# icyradio-exp-mmw-int-base.net
KiCad netlist of a schematic drawn in EAGLE
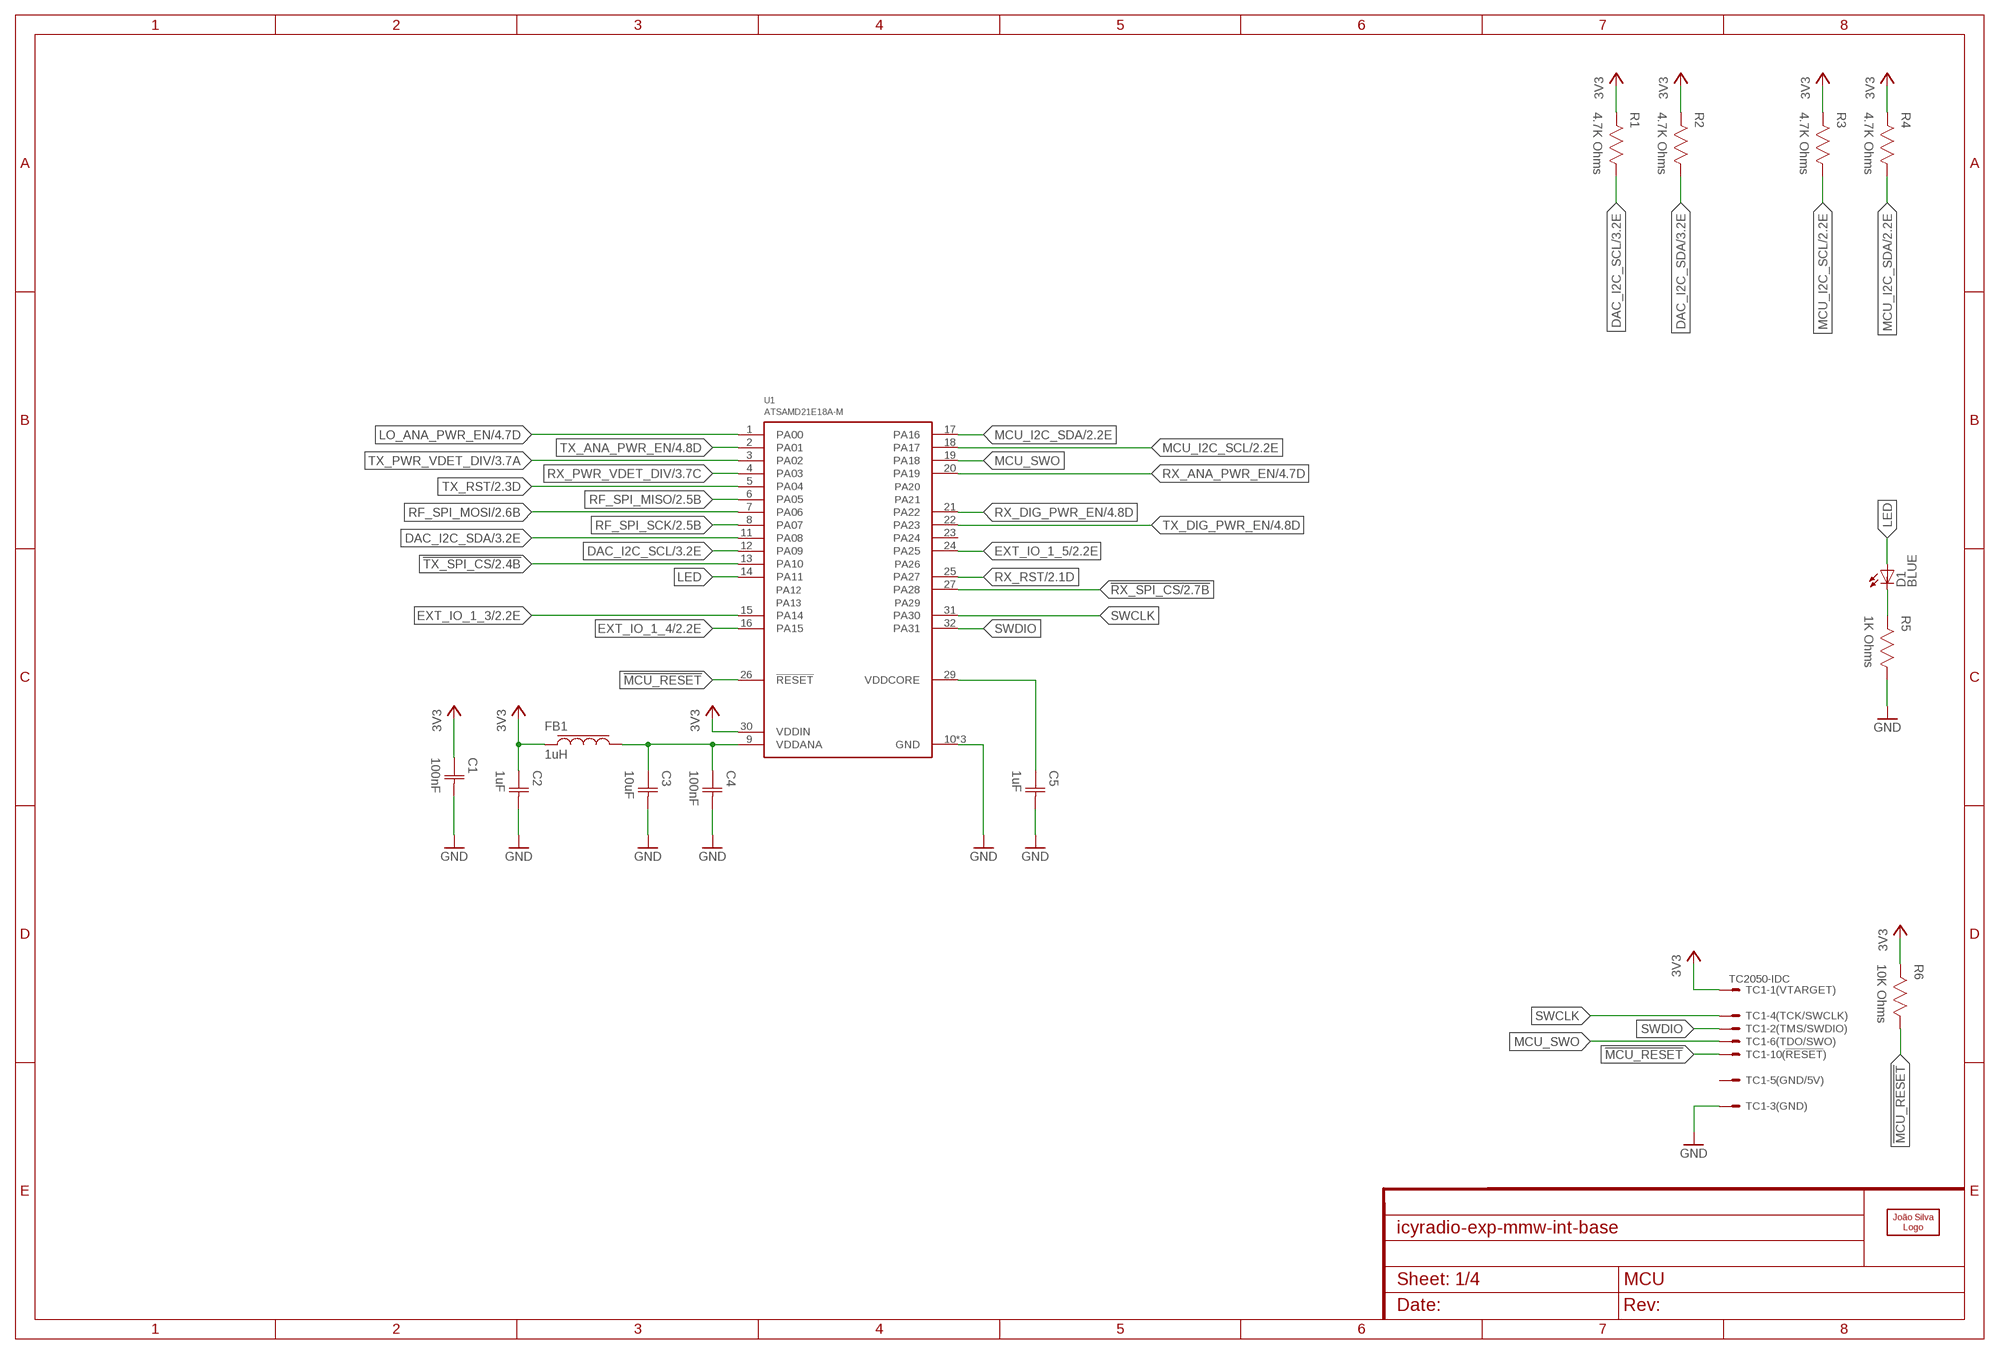
[diagram p0: schematic, sheet 1]
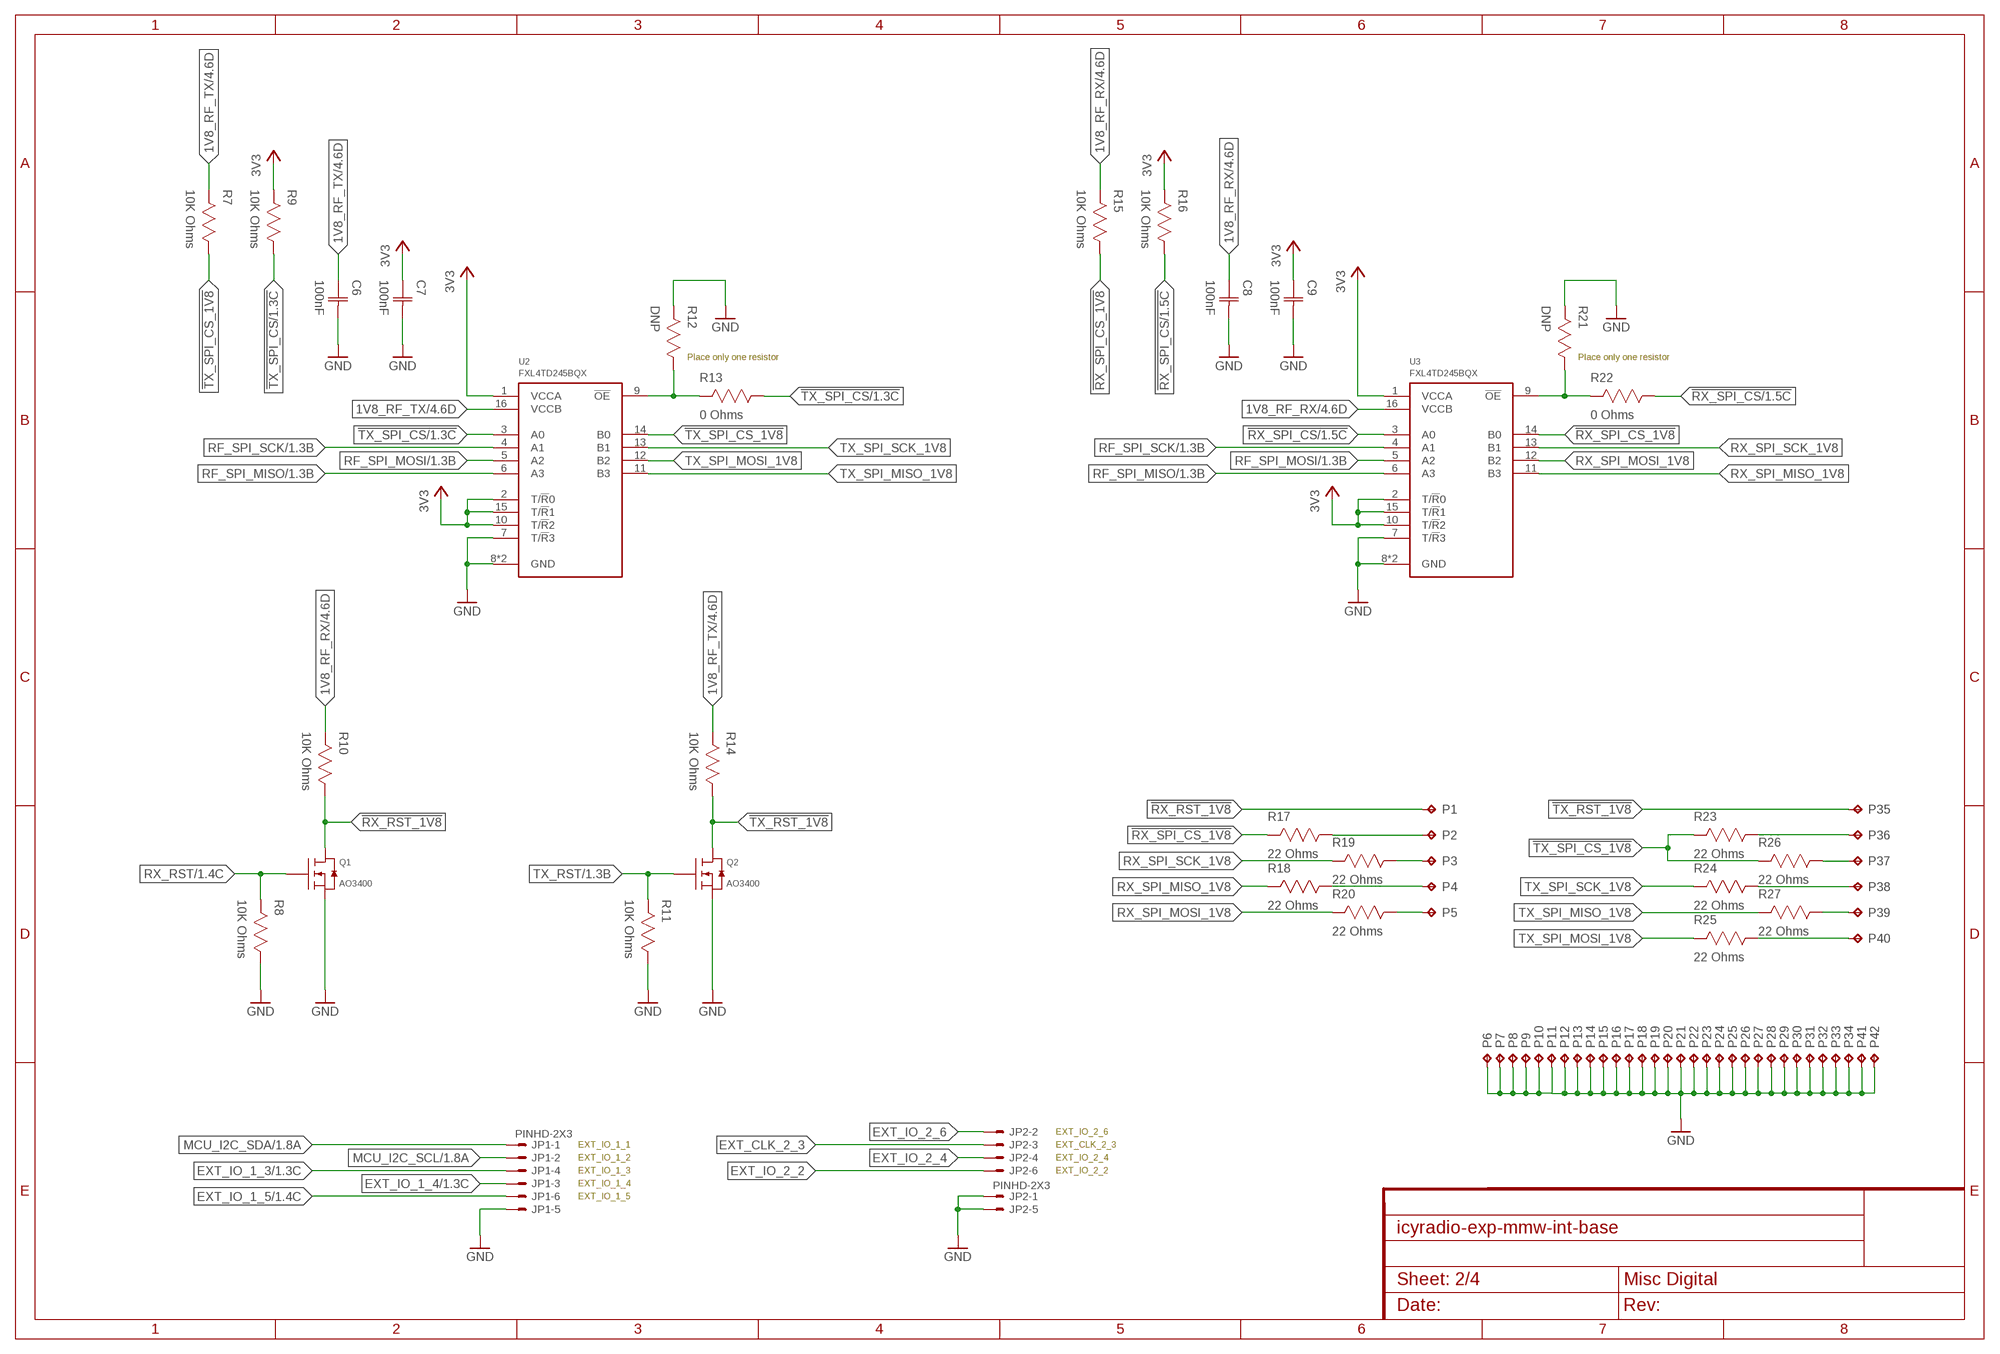
[diagram p1: schematic, sheet 2]
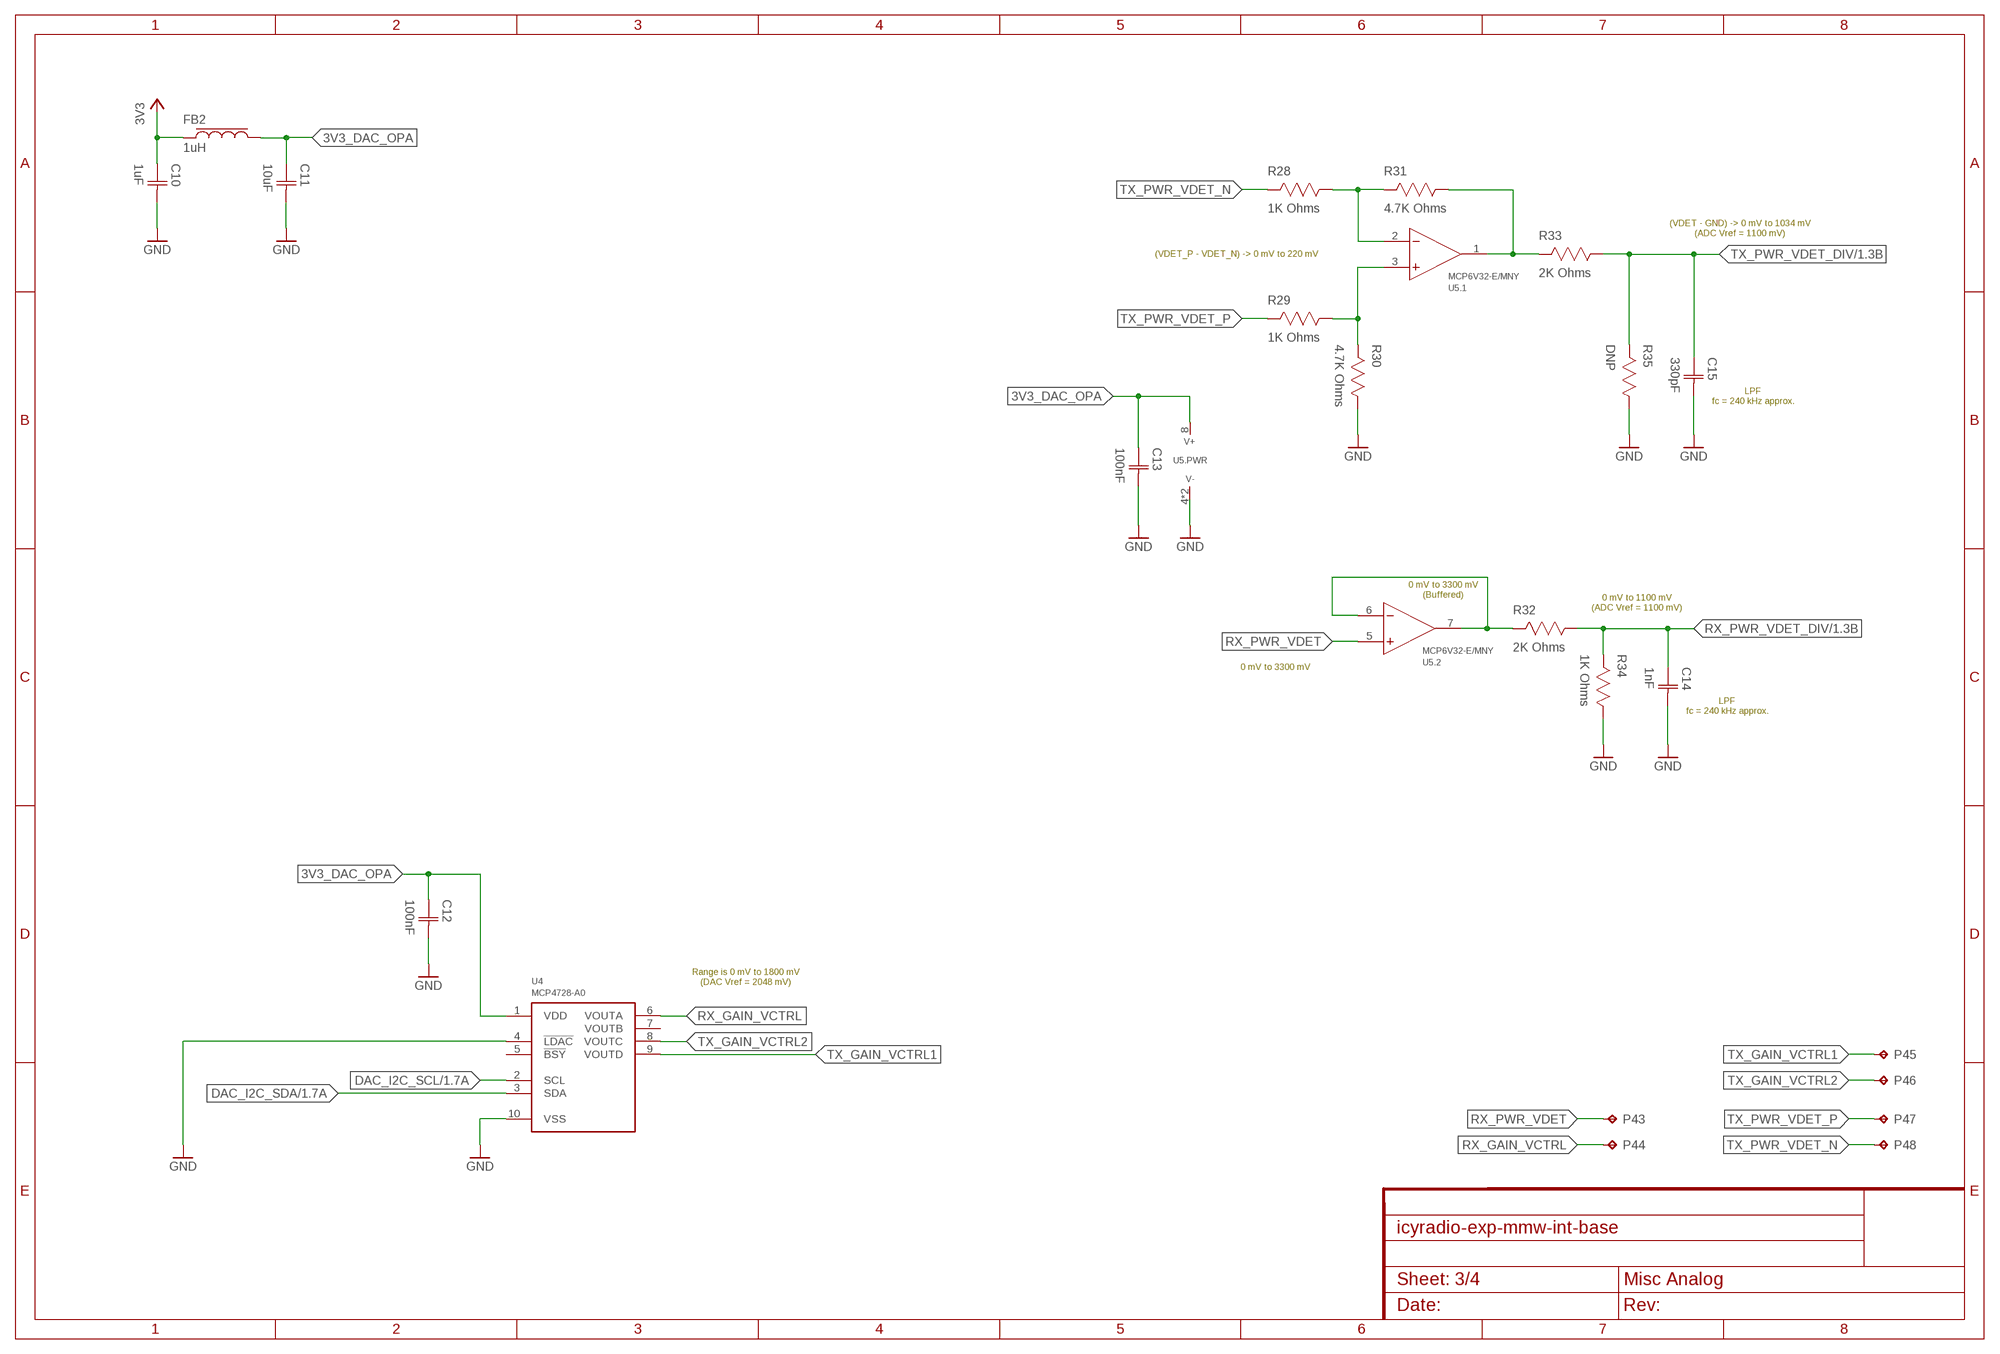
[diagram p2: schematic, sheet 3]
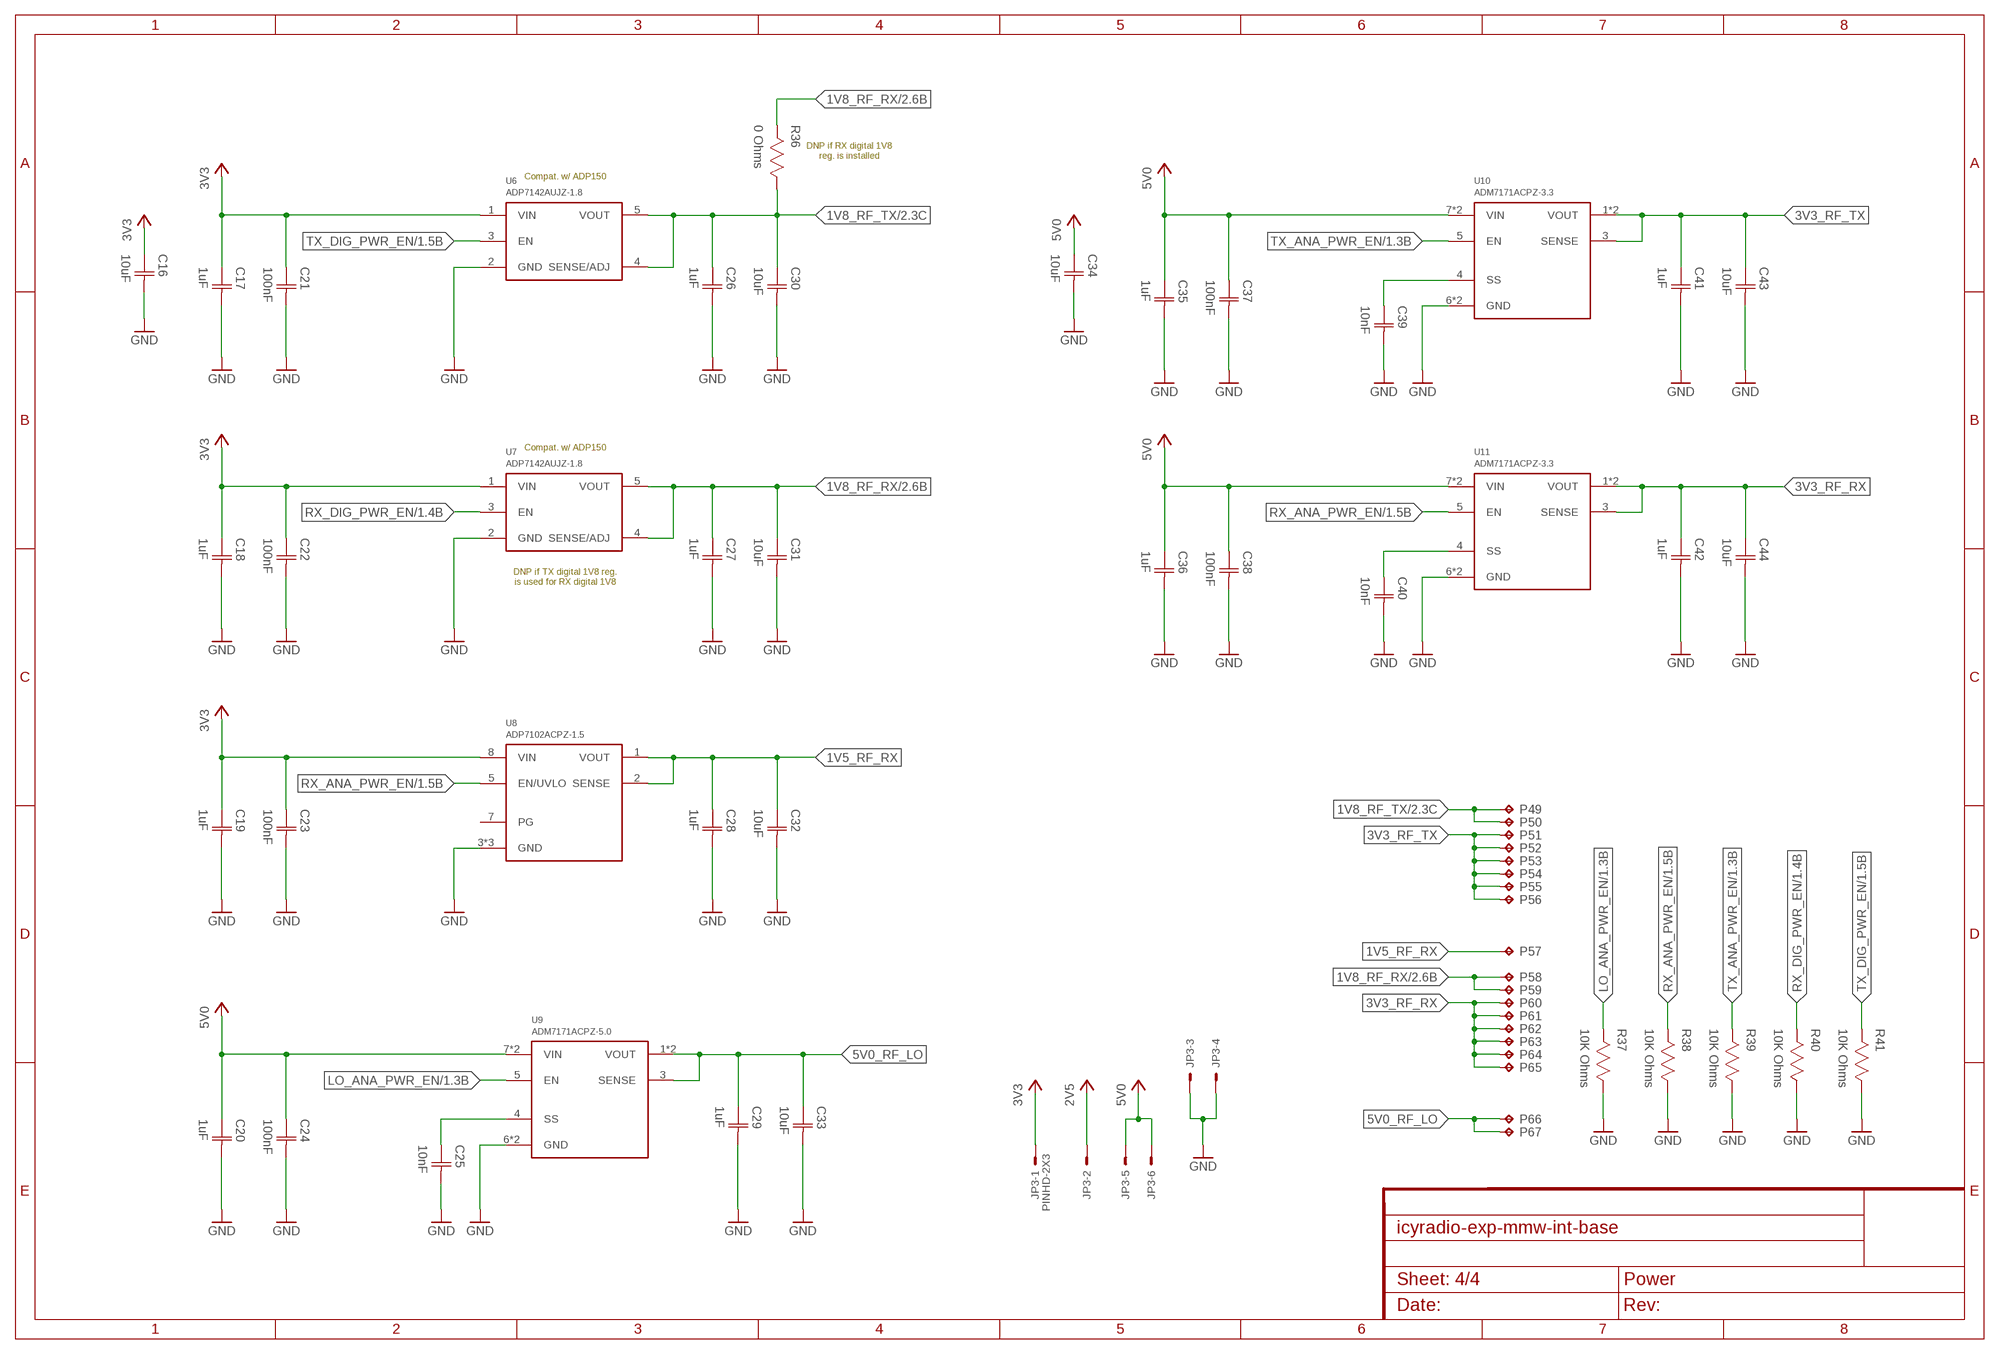
[diagram p3: schematic, sheet 4]

(export (version "E")
  (design (tool "Eeschema 10.0.6"))
  (components
    (comp (ref "C1")
      (value "100nF")
      (footprint "eagle-import:CAP0402")
      (libsource (lib "eagle-import") (part "CAPACITOR-0402"))
    )
    (comp (ref "C2")
      (value "1uF")
      (footprint "eagle-import:CAP0402")
      (libsource (lib "eagle-import") (part "CAPACITOR-0402"))
    )
    (comp (ref "C3")
      (value "10uF")
      (footprint "eagle-import:CAP0402")
      (libsource (lib "eagle-import") (part "CAPACITOR-0402"))
    )
    (comp (ref "C4")
      (value "100nF")
      (footprint "eagle-import:CAP0402")
      (libsource (lib "eagle-import") (part "CAPACITOR-0402"))
    )
    (comp (ref "C5")
      (value "1uF")
      (footprint "eagle-import:CAP0402")
      (libsource (lib "eagle-import") (part "CAPACITOR-0402"))
    )
    (comp (ref "D1")
      (value "LED0603")
      (footprint "eagle-import:0603")
      (fields (field (name "COLOR") "BLUE"))
      (libsource (lib "eagle-import") (part "LED0603"))
    )
    (comp (ref "FB1")
      (value "1uH")
      (footprint "eagle-import:IND0603")
      (libsource (lib "eagle-import") (part "FERRITE-0603"))
    )
    (comp (ref "LOGO1")
      (value "JSILVA-5MM")
      (footprint "eagle-import:JSILVA_5MM")
      (libsource (lib "eagle-import") (part "JSILVA-5MM"))
    )
    (comp (ref "R1")
      (value "4.7K Ohms")
      (footprint "eagle-import:RES0402")
      (libsource (lib "eagle-import") (part "RESISTOR-0402"))
    )
    (comp (ref "R2")
      (value "4.7K Ohms")
      (footprint "eagle-import:RES0402")
      (libsource (lib "eagle-import") (part "RESISTOR-0402"))
    )
    (comp (ref "R3")
      (value "4.7K Ohms")
      (footprint "eagle-import:RES0402")
      (libsource (lib "eagle-import") (part "RESISTOR-0402"))
    )
    (comp (ref "R4")
      (value "4.7K Ohms")
      (footprint "eagle-import:RES0402")
      (libsource (lib "eagle-import") (part "RESISTOR-0402"))
    )
    (comp (ref "R5")
      (value "1K Ohms")
      (footprint "eagle-import:RES0402")
      (libsource (lib "eagle-import") (part "RESISTOR-0402"))
    )
    (comp (ref "R6")
      (value "10K Ohms")
      (footprint "eagle-import:RES0402")
      (libsource (lib "eagle-import") (part "RESISTOR-0402"))
    )
    (comp (ref "TC1")
      (value "TC2050-IDC")
      (footprint "eagle-import:TC2050-IDC")
      (libsource (lib "eagle-import") (part "TC2050-IDC"))
    )
    (comp (ref "U1")
      (value "ATSAMD21E18A-M")
      (footprint "eagle-import:QFN32")
      (libsource (lib "eagle-import") (part "ATSAMD2-?M1E18A"))
    )
    (comp (ref "C6")
      (value "100nF")
      (footprint "eagle-import:CAP0402")
      (libsource (lib "eagle-import") (part "CAPACITOR-0402"))
    )
    (comp (ref "C7")
      (value "100nF")
      (footprint "eagle-import:CAP0402")
      (libsource (lib "eagle-import") (part "CAPACITOR-0402"))
    )
    (comp (ref "C8")
      (value "100nF")
      (footprint "eagle-import:CAP0402")
      (libsource (lib "eagle-import") (part "CAPACITOR-0402"))
    )
    (comp (ref "C9")
      (value "100nF")
      (footprint "eagle-import:CAP0402")
      (libsource (lib "eagle-import") (part "CAPACITOR-0402"))
    )
    (comp (ref "JP1")
      (value "PINHD-2X3")
      (footprint "eagle-import:2X03")
      (libsource (lib "eagle-import") (part "PINHD-2X3"))
    )
    (comp (ref "JP2")
      (value "PINHD-2X3")
      (footprint "eagle-import:2X03")
      (libsource (lib "eagle-import") (part "PINHD-2X3"))
    )
    (comp (ref "P1")
      (value "CHOLE-0.9MM-LAND")
      (footprint "eagle-import:CAST_HOLE_0P9MM_LAND")
      (libsource (lib "eagle-import") (part "CHOLE-0.9MM-LAND"))
    )
    (comp (ref "P2")
      (value "CHOLE-0.9MM-LAND")
      (footprint "eagle-import:CAST_HOLE_0P9MM_LAND")
      (libsource (lib "eagle-import") (part "CHOLE-0.9MM-LAND"))
    )
    (comp (ref "P3")
      (value "CHOLE-0.9MM-LAND")
      (footprint "eagle-import:CAST_HOLE_0P9MM_LAND")
      (libsource (lib "eagle-import") (part "CHOLE-0.9MM-LAND"))
    )
    (comp (ref "P4")
      (value "CHOLE-0.9MM-LAND")
      (footprint "eagle-import:CAST_HOLE_0P9MM_LAND")
      (libsource (lib "eagle-import") (part "CHOLE-0.9MM-LAND"))
    )
    (comp (ref "P5")
      (value "CHOLE-0.9MM-LAND")
      (footprint "eagle-import:CAST_HOLE_0P9MM_LAND")
      (libsource (lib "eagle-import") (part "CHOLE-0.9MM-LAND"))
    )
    (comp (ref "P6")
      (value "CHOLE-0.9MM-LAND")
      (footprint "eagle-import:CAST_HOLE_0P9MM_LAND")
      (libsource (lib "eagle-import") (part "CHOLE-0.9MM-LAND"))
    )
    (comp (ref "P7")
      (value "CHOLE-0.9MM-LAND")
      (footprint "eagle-import:CAST_HOLE_0P9MM_LAND")
      (libsource (lib "eagle-import") (part "CHOLE-0.9MM-LAND"))
    )
    (comp (ref "P8")
      (value "CHOLE-0.9MM-LAND")
      (footprint "eagle-import:CAST_HOLE_0P9MM_LAND")
      (libsource (lib "eagle-import") (part "CHOLE-0.9MM-LAND"))
    )
    (comp (ref "P9")
      (value "CHOLE-0.9MM-LAND")
      (footprint "eagle-import:CAST_HOLE_0P9MM_LAND")
      (libsource (lib "eagle-import") (part "CHOLE-0.9MM-LAND"))
    )
    (comp (ref "P10")
      (value "CHOLE-0.9MM-LAND")
      (footprint "eagle-import:CAST_HOLE_0P9MM_LAND")
      (libsource (lib "eagle-import") (part "CHOLE-0.9MM-LAND"))
    )
    (comp (ref "P11")
      (value "CHOLE-0.9MM-LAND")
      (footprint "eagle-import:CAST_HOLE_0P9MM_LAND")
      (libsource (lib "eagle-import") (part "CHOLE-0.9MM-LAND"))
    )
    (comp (ref "P12")
      (value "CHOLE-0.9MM-LAND")
      (footprint "eagle-import:CAST_HOLE_0P9MM_LAND")
      (libsource (lib "eagle-import") (part "CHOLE-0.9MM-LAND"))
    )
    (comp (ref "P13")
      (value "CHOLE-0.9MM-LAND")
      (footprint "eagle-import:CAST_HOLE_0P9MM_LAND")
      (libsource (lib "eagle-import") (part "CHOLE-0.9MM-LAND"))
    )
    (comp (ref "P14")
      (value "CHOLE-0.9MM-LAND")
      (footprint "eagle-import:CAST_HOLE_0P9MM_LAND")
      (libsource (lib "eagle-import") (part "CHOLE-0.9MM-LAND"))
    )
    (comp (ref "P15")
      (value "CHOLE-0.9MM-LAND")
      (footprint "eagle-import:CAST_HOLE_0P9MM_LAND")
      (libsource (lib "eagle-import") (part "CHOLE-0.9MM-LAND"))
    )
    (comp (ref "P16")
      (value "CHOLE-0.9MM-LAND")
      (footprint "eagle-import:CAST_HOLE_0P9MM_LAND")
      (libsource (lib "eagle-import") (part "CHOLE-0.9MM-LAND"))
    )
    (comp (ref "P17")
      (value "CHOLE-0.9MM-LAND")
      (footprint "eagle-import:CAST_HOLE_0P9MM_LAND")
      (libsource (lib "eagle-import") (part "CHOLE-0.9MM-LAND"))
    )
    (comp (ref "P18")
      (value "CHOLE-0.9MM-LAND")
      (footprint "eagle-import:CAST_HOLE_0P9MM_LAND")
      (libsource (lib "eagle-import") (part "CHOLE-0.9MM-LAND"))
    )
    (comp (ref "P19")
      (value "CHOLE-0.9MM-LAND")
      (footprint "eagle-import:CAST_HOLE_0P9MM_LAND")
      (libsource (lib "eagle-import") (part "CHOLE-0.9MM-LAND"))
    )
    (comp (ref "P20")
      (value "CHOLE-0.9MM-LAND")
      (footprint "eagle-import:CAST_HOLE_0P9MM_LAND")
      (libsource (lib "eagle-import") (part "CHOLE-0.9MM-LAND"))
    )
    (comp (ref "P21")
      (value "CHOLE-0.9MM-LAND")
      (footprint "eagle-import:CAST_HOLE_0P9MM_LAND")
      (libsource (lib "eagle-import") (part "CHOLE-0.9MM-LAND"))
    )
    (comp (ref "P22")
      (value "CHOLE-0.9MM-LAND")
      (footprint "eagle-import:CAST_HOLE_0P9MM_LAND")
      (libsource (lib "eagle-import") (part "CHOLE-0.9MM-LAND"))
    )
    (comp (ref "P23")
      (value "CHOLE-0.9MM-LAND")
      (footprint "eagle-import:CAST_HOLE_0P9MM_LAND")
      (libsource (lib "eagle-import") (part "CHOLE-0.9MM-LAND"))
    )
    (comp (ref "P24")
      (value "CHOLE-0.9MM-LAND")
      (footprint "eagle-import:CAST_HOLE_0P9MM_LAND")
      (libsource (lib "eagle-import") (part "CHOLE-0.9MM-LAND"))
    )
    (comp (ref "P25")
      (value "CHOLE-0.9MM-LAND")
      (footprint "eagle-import:CAST_HOLE_0P9MM_LAND")
      (libsource (lib "eagle-import") (part "CHOLE-0.9MM-LAND"))
    )
    (comp (ref "P26")
      (value "CHOLE-0.9MM-LAND")
      (footprint "eagle-import:CAST_HOLE_0P9MM_LAND")
      (libsource (lib "eagle-import") (part "CHOLE-0.9MM-LAND"))
    )
    (comp (ref "P27")
      (value "CHOLE-0.9MM-LAND")
      (footprint "eagle-import:CAST_HOLE_0P9MM_LAND")
      (libsource (lib "eagle-import") (part "CHOLE-0.9MM-LAND"))
    )
    (comp (ref "P28")
      (value "CHOLE-0.9MM-LAND")
      (footprint "eagle-import:CAST_HOLE_0P9MM_LAND")
      (libsource (lib "eagle-import") (part "CHOLE-0.9MM-LAND"))
    )
    (comp (ref "P29")
      (value "CHOLE-0.9MM-LAND")
      (footprint "eagle-import:CAST_HOLE_0P9MM_LAND")
      (libsource (lib "eagle-import") (part "CHOLE-0.9MM-LAND"))
    )
    (comp (ref "P30")
      (value "CHOLE-0.9MM-LAND")
      (footprint "eagle-import:CAST_HOLE_0P9MM_LAND")
      (libsource (lib "eagle-import") (part "CHOLE-0.9MM-LAND"))
    )
    (comp (ref "P31")
      (value "CHOLE-0.9MM-LAND")
      (footprint "eagle-import:CAST_HOLE_0P9MM_LAND")
      (libsource (lib "eagle-import") (part "CHOLE-0.9MM-LAND"))
    )
    (comp (ref "P32")
      (value "CHOLE-0.9MM-LAND")
      (footprint "eagle-import:CAST_HOLE_0P9MM_LAND")
      (libsource (lib "eagle-import") (part "CHOLE-0.9MM-LAND"))
    )
    (comp (ref "P33")
      (value "CHOLE-0.9MM-LAND")
      (footprint "eagle-import:CAST_HOLE_0P9MM_LAND")
      (libsource (lib "eagle-import") (part "CHOLE-0.9MM-LAND"))
    )
    (comp (ref "P34")
      (value "CHOLE-0.9MM-LAND")
      (footprint "eagle-import:CAST_HOLE_0P9MM_LAND")
      (libsource (lib "eagle-import") (part "CHOLE-0.9MM-LAND"))
    )
    (comp (ref "P35")
      (value "CHOLE-0.9MM-LAND")
      (footprint "eagle-import:CAST_HOLE_0P9MM_LAND")
      (libsource (lib "eagle-import") (part "CHOLE-0.9MM-LAND"))
    )
    (comp (ref "P36")
      (value "CHOLE-0.9MM-LAND")
      (footprint "eagle-import:CAST_HOLE_0P9MM_LAND")
      (libsource (lib "eagle-import") (part "CHOLE-0.9MM-LAND"))
    )
    (comp (ref "P37")
      (value "CHOLE-0.9MM-LAND")
      (footprint "eagle-import:CAST_HOLE_0P9MM_LAND")
      (libsource (lib "eagle-import") (part "CHOLE-0.9MM-LAND"))
    )
    (comp (ref "P38")
      (value "CHOLE-0.9MM-LAND")
      (footprint "eagle-import:CAST_HOLE_0P9MM_LAND")
      (libsource (lib "eagle-import") (part "CHOLE-0.9MM-LAND"))
    )
    (comp (ref "P39")
      (value "CHOLE-0.9MM-LAND")
      (footprint "eagle-import:CAST_HOLE_0P9MM_LAND")
      (libsource (lib "eagle-import") (part "CHOLE-0.9MM-LAND"))
    )
    (comp (ref "P40")
      (value "CHOLE-0.9MM-LAND")
      (footprint "eagle-import:CAST_HOLE_0P9MM_LAND")
      (libsource (lib "eagle-import") (part "CHOLE-0.9MM-LAND"))
    )
    (comp (ref "P41")
      (value "CHOLE-0.9MM-LAND")
      (footprint "eagle-import:CAST_HOLE_0P9MM_LAND")
      (libsource (lib "eagle-import") (part "CHOLE-0.9MM-LAND"))
    )
    (comp (ref "P42")
      (value "CHOLE-0.9MM-LAND")
      (footprint "eagle-import:CAST_HOLE_0P9MM_LAND")
      (libsource (lib "eagle-import") (part "CHOLE-0.9MM-LAND"))
    )
    (comp (ref "Q1")
      (value "AO3400")
      (footprint "eagle-import:SOT23")
      (libsource (lib "eagle-import") (part "AO3400"))
    )
    (comp (ref "Q2")
      (value "AO3400")
      (footprint "eagle-import:SOT23")
      (libsource (lib "eagle-import") (part "AO3400"))
    )
    (comp (ref "R7")
      (value "10K Ohms")
      (footprint "eagle-import:RES0402")
      (libsource (lib "eagle-import") (part "RESISTOR-0402"))
    )
    (comp (ref "R8")
      (value "10K Ohms")
      (footprint "eagle-import:RES0402")
      (libsource (lib "eagle-import") (part "RESISTOR-0402"))
    )
    (comp (ref "R9")
      (value "10K Ohms")
      (footprint "eagle-import:RES0402")
      (libsource (lib "eagle-import") (part "RESISTOR-0402"))
    )
    (comp (ref "R10")
      (value "10K Ohms")
      (footprint "eagle-import:RES0402")
      (libsource (lib "eagle-import") (part "RESISTOR-0402"))
    )
    (comp (ref "R11")
      (value "10K Ohms")
      (footprint "eagle-import:RES0402")
      (libsource (lib "eagle-import") (part "RESISTOR-0402"))
    )
    (comp (ref "R12")
      (value "DNP")
      (footprint "eagle-import:RES0402")
      (libsource (lib "eagle-import") (part "RESISTOR-0402"))
    )
    (comp (ref "R13")
      (value "0 Ohms")
      (footprint "eagle-import:RES0402")
      (libsource (lib "eagle-import") (part "RESISTOR-0402"))
    )
    (comp (ref "R14")
      (value "10K Ohms")
      (footprint "eagle-import:RES0402")
      (libsource (lib "eagle-import") (part "RESISTOR-0402"))
    )
    (comp (ref "R15")
      (value "10K Ohms")
      (footprint "eagle-import:RES0402")
      (libsource (lib "eagle-import") (part "RESISTOR-0402"))
    )
    (comp (ref "R16")
      (value "10K Ohms")
      (footprint "eagle-import:RES0402")
      (libsource (lib "eagle-import") (part "RESISTOR-0402"))
    )
    (comp (ref "R17")
      (value "22 Ohms")
      (footprint "eagle-import:RES0402")
      (libsource (lib "eagle-import") (part "RESISTOR-0402"))
    )
    (comp (ref "R18")
      (value "22 Ohms")
      (footprint "eagle-import:RES0402")
      (libsource (lib "eagle-import") (part "RESISTOR-0402"))
    )
    (comp (ref "R19")
      (value "22 Ohms")
      (footprint "eagle-import:RES0402")
      (libsource (lib "eagle-import") (part "RESISTOR-0402"))
    )
    (comp (ref "R20")
      (value "22 Ohms")
      (footprint "eagle-import:RES0402")
      (libsource (lib "eagle-import") (part "RESISTOR-0402"))
    )
    (comp (ref "R21")
      (value "DNP")
      (footprint "eagle-import:RES0402")
      (libsource (lib "eagle-import") (part "RESISTOR-0402"))
    )
    (comp (ref "R22")
      (value "0 Ohms")
      (footprint "eagle-import:RES0402")
      (libsource (lib "eagle-import") (part "RESISTOR-0402"))
    )
    (comp (ref "R23")
      (value "22 Ohms")
      (footprint "eagle-import:RES0402")
      (libsource (lib "eagle-import") (part "RESISTOR-0402"))
    )
    (comp (ref "R24")
      (value "22 Ohms")
      (footprint "eagle-import:RES0402")
      (libsource (lib "eagle-import") (part "RESISTOR-0402"))
    )
    (comp (ref "R25")
      (value "22 Ohms")
      (footprint "eagle-import:RES0402")
      (libsource (lib "eagle-import") (part "RESISTOR-0402"))
    )
    (comp (ref "R26")
      (value "22 Ohms")
      (footprint "eagle-import:RES0402")
      (libsource (lib "eagle-import") (part "RESISTOR-0402"))
    )
    (comp (ref "R27")
      (value "22 Ohms")
      (footprint "eagle-import:RES0402")
      (libsource (lib "eagle-import") (part "RESISTOR-0402"))
    )
    (comp (ref "U2")
      (value "FXL4TD245BQX")
      (footprint "eagle-import:DQFN16")
      (libsource (lib "eagle-import") (part "FXL4TD245BQX"))
    )
    (comp (ref "U3")
      (value "FXL4TD245BQX")
      (footprint "eagle-import:DQFN16")
      (libsource (lib "eagle-import") (part "FXL4TD245BQX"))
    )
    (comp (ref "C16")
      (value "10uF")
      (footprint "eagle-import:CAP0603")
      (libsource (lib "eagle-import") (part "CAPACITOR-0603"))
    )
    (comp (ref "C17")
      (value "1uF")
      (footprint "eagle-import:CAP0402")
      (libsource (lib "eagle-import") (part "CAPACITOR-0402"))
    )
    (comp (ref "C18")
      (value "1uF")
      (footprint "eagle-import:CAP0402")
      (libsource (lib "eagle-import") (part "CAPACITOR-0402"))
    )
    (comp (ref "C19")
      (value "1uF")
      (footprint "eagle-import:CAP0402")
      (libsource (lib "eagle-import") (part "CAPACITOR-0402"))
    )
    (comp (ref "C20")
      (value "1uF")
      (footprint "eagle-import:CAP0402")
      (libsource (lib "eagle-import") (part "CAPACITOR-0402"))
    )
    (comp (ref "C21")
      (value "100nF")
      (footprint "eagle-import:CAP0402")
      (libsource (lib "eagle-import") (part "CAPACITOR-0402"))
    )
    (comp (ref "C22")
      (value "100nF")
      (footprint "eagle-import:CAP0402")
      (libsource (lib "eagle-import") (part "CAPACITOR-0402"))
    )
    (comp (ref "C23")
      (value "100nF")
      (footprint "eagle-import:CAP0402")
      (libsource (lib "eagle-import") (part "CAPACITOR-0402"))
    )
    (comp (ref "C24")
      (value "100nF")
      (footprint "eagle-import:CAP0402")
      (libsource (lib "eagle-import") (part "CAPACITOR-0402"))
    )
    (comp (ref "C25")
      (value "10nF")
      (footprint "eagle-import:CAP0402")
      (libsource (lib "eagle-import") (part "CAPACITOR-0402"))
    )
    (comp (ref "C26")
      (value "1uF")
      (footprint "eagle-import:CAP0402")
      (libsource (lib "eagle-import") (part "CAPACITOR-0402"))
    )
    (comp (ref "C27")
      (value "1uF")
      (footprint "eagle-import:CAP0402")
      (libsource (lib "eagle-import") (part "CAPACITOR-0402"))
    )
    (comp (ref "C28")
      (value "1uF")
      (footprint "eagle-import:CAP0402")
      (libsource (lib "eagle-import") (part "CAPACITOR-0402"))
    )
    (comp (ref "C29")
      (value "1uF")
      (footprint "eagle-import:CAP0402")
      (libsource (lib "eagle-import") (part "CAPACITOR-0402"))
    )
    (comp (ref "C30")
      (value "10uF")
      (footprint "eagle-import:CAP0402")
      (libsource (lib "eagle-import") (part "CAPACITOR-0402"))
    )
    (comp (ref "C31")
      (value "10uF")
      (footprint "eagle-import:CAP0402")
      (libsource (lib "eagle-import") (part "CAPACITOR-0402"))
    )
    (comp (ref "C32")
      (value "10uF")
      (footprint "eagle-import:CAP0402")
      (libsource (lib "eagle-import") (part "CAPACITOR-0402"))
    )
    (comp (ref "C33")
      (value "10uF")
      (footprint "eagle-import:CAP0402")
      (libsource (lib "eagle-import") (part "CAPACITOR-0402"))
    )
    (comp (ref "C34")
      (value "10uF")
      (footprint "eagle-import:CAP0603")
      (libsource (lib "eagle-import") (part "CAPACITOR-0603"))
    )
    (comp (ref "C35")
      (value "1uF")
      (footprint "eagle-import:CAP0402")
      (libsource (lib "eagle-import") (part "CAPACITOR-0402"))
    )
    (comp (ref "C36")
      (value "1uF")
      (footprint "eagle-import:CAP0402")
      (libsource (lib "eagle-import") (part "CAPACITOR-0402"))
    )
    (comp (ref "C37")
      (value "100nF")
      (footprint "eagle-import:CAP0402")
      (libsource (lib "eagle-import") (part "CAPACITOR-0402"))
    )
    (comp (ref "C38")
      (value "100nF")
      (footprint "eagle-import:CAP0402")
      (libsource (lib "eagle-import") (part "CAPACITOR-0402"))
    )
    (comp (ref "C39")
      (value "10nF")
      (footprint "eagle-import:CAP0402")
      (libsource (lib "eagle-import") (part "CAPACITOR-0402"))
    )
    (comp (ref "C40")
      (value "10nF")
      (footprint "eagle-import:CAP0402")
      (libsource (lib "eagle-import") (part "CAPACITOR-0402"))
    )
    (comp (ref "C41")
      (value "1uF")
      (footprint "eagle-import:CAP0402")
      (libsource (lib "eagle-import") (part "CAPACITOR-0402"))
    )
    (comp (ref "C42")
      (value "1uF")
      (footprint "eagle-import:CAP0402")
      (libsource (lib "eagle-import") (part "CAPACITOR-0402"))
    )
    (comp (ref "C43")
      (value "10uF")
      (footprint "eagle-import:CAP0402")
      (libsource (lib "eagle-import") (part "CAPACITOR-0402"))
    )
    (comp (ref "C44")
      (value "10uF")
      (footprint "eagle-import:CAP0402")
      (libsource (lib "eagle-import") (part "CAPACITOR-0402"))
    )
    (comp (ref "JP3")
      (value "PINHD-2X3")
      (footprint "eagle-import:2X03")
      (libsource (lib "eagle-import") (part "PINHD-2X3"))
    )
    (comp (ref "P49")
      (value "CHOLE-0.9MM-LAND")
      (footprint "eagle-import:CAST_HOLE_0P9MM_LAND")
      (libsource (lib "eagle-import") (part "CHOLE-0.9MM-LAND"))
    )
    (comp (ref "P50")
      (value "CHOLE-0.9MM-LAND")
      (footprint "eagle-import:CAST_HOLE_0P9MM_LAND")
      (libsource (lib "eagle-import") (part "CHOLE-0.9MM-LAND"))
    )
    (comp (ref "P51")
      (value "CHOLE-0.9MM-LAND")
      (footprint "eagle-import:CAST_HOLE_0P9MM_LAND")
      (libsource (lib "eagle-import") (part "CHOLE-0.9MM-LAND"))
    )
    (comp (ref "P52")
      (value "CHOLE-0.9MM-LAND")
      (footprint "eagle-import:CAST_HOLE_0P9MM_LAND")
      (libsource (lib "eagle-import") (part "CHOLE-0.9MM-LAND"))
    )
    (comp (ref "P53")
      (value "CHOLE-0.9MM-LAND")
      (footprint "eagle-import:CAST_HOLE_0P9MM_LAND")
      (libsource (lib "eagle-import") (part "CHOLE-0.9MM-LAND"))
    )
    (comp (ref "P54")
      (value "CHOLE-0.9MM-LAND")
      (footprint "eagle-import:CAST_HOLE_0P9MM_LAND")
      (libsource (lib "eagle-import") (part "CHOLE-0.9MM-LAND"))
    )
    (comp (ref "P55")
      (value "CHOLE-0.9MM-LAND")
      (footprint "eagle-import:CAST_HOLE_0P9MM_LAND")
      (libsource (lib "eagle-import") (part "CHOLE-0.9MM-LAND"))
    )
    (comp (ref "P56")
      (value "CHOLE-0.9MM-LAND")
      (footprint "eagle-import:CAST_HOLE_0P9MM_LAND")
      (libsource (lib "eagle-import") (part "CHOLE-0.9MM-LAND"))
    )
    (comp (ref "P57")
      (value "CHOLE-0.9MM-LAND")
      (footprint "eagle-import:CAST_HOLE_0P9MM_LAND")
      (libsource (lib "eagle-import") (part "CHOLE-0.9MM-LAND"))
    )
    (comp (ref "P58")
      (value "CHOLE-0.9MM-LAND")
      (footprint "eagle-import:CAST_HOLE_0P9MM_LAND")
      (libsource (lib "eagle-import") (part "CHOLE-0.9MM-LAND"))
    )
    (comp (ref "P59")
      (value "CHOLE-0.9MM-LAND")
      (footprint "eagle-import:CAST_HOLE_0P9MM_LAND")
      (libsource (lib "eagle-import") (part "CHOLE-0.9MM-LAND"))
    )
    (comp (ref "P60")
      (value "CHOLE-0.9MM-LAND")
      (footprint "eagle-import:CAST_HOLE_0P9MM_LAND")
      (libsource (lib "eagle-import") (part "CHOLE-0.9MM-LAND"))
    )
    (comp (ref "P61")
      (value "CHOLE-0.9MM-LAND")
      (footprint "eagle-import:CAST_HOLE_0P9MM_LAND")
      (libsource (lib "eagle-import") (part "CHOLE-0.9MM-LAND"))
    )
    (comp (ref "P62")
      (value "CHOLE-0.9MM-LAND")
      (footprint "eagle-import:CAST_HOLE_0P9MM_LAND")
      (libsource (lib "eagle-import") (part "CHOLE-0.9MM-LAND"))
    )
    (comp (ref "P63")
      (value "CHOLE-0.9MM-LAND")
      (footprint "eagle-import:CAST_HOLE_0P9MM_LAND")
      (libsource (lib "eagle-import") (part "CHOLE-0.9MM-LAND"))
    )
    (comp (ref "P64")
      (value "CHOLE-0.9MM-LAND")
      (footprint "eagle-import:CAST_HOLE_0P9MM_LAND")
      (libsource (lib "eagle-import") (part "CHOLE-0.9MM-LAND"))
    )
    (comp (ref "P65")
      (value "CHOLE-0.9MM-LAND")
      (footprint "eagle-import:CAST_HOLE_0P9MM_LAND")
      (libsource (lib "eagle-import") (part "CHOLE-0.9MM-LAND"))
    )
    (comp (ref "P66")
      (value "CHOLE-0.9MM-LAND")
      (footprint "eagle-import:CAST_HOLE_0P9MM_LAND")
      (libsource (lib "eagle-import") (part "CHOLE-0.9MM-LAND"))
    )
    (comp (ref "P67")
      (value "CHOLE-0.9MM-LAND")
      (footprint "eagle-import:CAST_HOLE_0P9MM_LAND")
      (libsource (lib "eagle-import") (part "CHOLE-0.9MM-LAND"))
    )
    (comp (ref "R36")
      (value "0 Ohms")
      (footprint "eagle-import:RES0402")
      (libsource (lib "eagle-import") (part "RESISTOR-0402"))
    )
    (comp (ref "R37")
      (value "10K Ohms")
      (footprint "eagle-import:RES0402")
      (libsource (lib "eagle-import") (part "RESISTOR-0402"))
    )
    (comp (ref "R38")
      (value "10K Ohms")
      (footprint "eagle-import:RES0402")
      (libsource (lib "eagle-import") (part "RESISTOR-0402"))
    )
    (comp (ref "R39")
      (value "10K Ohms")
      (footprint "eagle-import:RES0402")
      (libsource (lib "eagle-import") (part "RESISTOR-0402"))
    )
    (comp (ref "R40")
      (value "10K Ohms")
      (footprint "eagle-import:RES0402")
      (libsource (lib "eagle-import") (part "RESISTOR-0402"))
    )
    (comp (ref "R41")
      (value "10K Ohms")
      (footprint "eagle-import:RES0402")
      (libsource (lib "eagle-import") (part "RESISTOR-0402"))
    )
    (comp (ref "U6")
      (value "ADP7142AUJZ-1.8")
      (footprint "eagle-import:SOT23-5")
      (libsource (lib "eagle-import") (part "ADP7142AUJZ-1.8"))
    )
    (comp (ref "U7")
      (value "ADP7142AUJZ-1.8")
      (footprint "eagle-import:SOT23-5")
      (libsource (lib "eagle-import") (part "ADP7142AUJZ-1.8"))
    )
    (comp (ref "U8")
      (value "ADP7102ACPZ-1.5")
      (footprint "eagle-import:LFCSP8_3X3")
      (libsource (lib "eagle-import") (part "ADP7102ACPZ-1.5"))
    )
    (comp (ref "U9")
      (value "ADM7171ACPZ-5.0")
      (footprint "eagle-import:LFCSP8_3X3")
      (libsource (lib "eagle-import") (part "ADM7171ACPZ-5.0"))
    )
    (comp (ref "U10")
      (value "ADM7171ACPZ-3.3")
      (footprint "eagle-import:LFCSP8_3X3")
      (libsource (lib "eagle-import") (part "ADM7171ACPZ-3.3"))
    )
    (comp (ref "U11")
      (value "ADM7171ACPZ-3.3")
      (footprint "eagle-import:LFCSP8_3X3")
      (libsource (lib "eagle-import") (part "ADM7171ACPZ-3.3"))
    )
    (comp (ref "C10")
      (value "1uF")
      (footprint "eagle-import:CAP0402")
      (libsource (lib "eagle-import") (part "CAPACITOR-0402"))
    )
    (comp (ref "C11")
      (value "10uF")
      (footprint "eagle-import:CAP0402")
      (libsource (lib "eagle-import") (part "CAPACITOR-0402"))
    )
    (comp (ref "C12")
      (value "100nF")
      (footprint "eagle-import:CAP0402")
      (libsource (lib "eagle-import") (part "CAPACITOR-0402"))
    )
    (comp (ref "C13")
      (value "100nF")
      (footprint "eagle-import:CAP0402")
      (libsource (lib "eagle-import") (part "CAPACITOR-0402"))
    )
    (comp (ref "C14")
      (value "1nF")
      (footprint "eagle-import:CAP0402")
      (libsource (lib "eagle-import") (part "CAPACITOR-0402"))
    )
    (comp (ref "C15")
      (value "330pF")
      (footprint "eagle-import:CAP0402")
      (libsource (lib "eagle-import") (part "CAPACITOR-0402"))
    )
    (comp (ref "FB2")
      (value "1uH")
      (footprint "eagle-import:IND0603")
      (libsource (lib "eagle-import") (part "FERRITE-0603"))
    )
    (comp (ref "P43")
      (value "CHOLE-0.9MM-LAND")
      (footprint "eagle-import:CAST_HOLE_0P9MM_LAND")
      (libsource (lib "eagle-import") (part "CHOLE-0.9MM-LAND"))
    )
    (comp (ref "P44")
      (value "CHOLE-0.9MM-LAND")
      (footprint "eagle-import:CAST_HOLE_0P9MM_LAND")
      (libsource (lib "eagle-import") (part "CHOLE-0.9MM-LAND"))
    )
    (comp (ref "P45")
      (value "CHOLE-0.9MM-LAND")
      (footprint "eagle-import:CAST_HOLE_0P9MM_LAND")
      (libsource (lib "eagle-import") (part "CHOLE-0.9MM-LAND"))
    )
    (comp (ref "P46")
      (value "CHOLE-0.9MM-LAND")
      (footprint "eagle-import:CAST_HOLE_0P9MM_LAND")
      (libsource (lib "eagle-import") (part "CHOLE-0.9MM-LAND"))
    )
    (comp (ref "P47")
      (value "CHOLE-0.9MM-LAND")
      (footprint "eagle-import:CAST_HOLE_0P9MM_LAND")
      (libsource (lib "eagle-import") (part "CHOLE-0.9MM-LAND"))
    )
    (comp (ref "P48")
      (value "CHOLE-0.9MM-LAND")
      (footprint "eagle-import:CAST_HOLE_0P9MM_LAND")
      (libsource (lib "eagle-import") (part "CHOLE-0.9MM-LAND"))
    )
    (comp (ref "R28")
      (value "1K Ohms")
      (footprint "eagle-import:RES0402")
      (libsource (lib "eagle-import") (part "RESISTOR-0402"))
    )
    (comp (ref "R29")
      (value "1K Ohms")
      (footprint "eagle-import:RES0402")
      (libsource (lib "eagle-import") (part "RESISTOR-0402"))
    )
    (comp (ref "R30")
      (value "4.7K Ohms")
      (footprint "eagle-import:RES0402")
      (libsource (lib "eagle-import") (part "RESISTOR-0402"))
    )
    (comp (ref "R31")
      (value "4.7K Ohms")
      (footprint "eagle-import:RES0402")
      (libsource (lib "eagle-import") (part "RESISTOR-0402"))
    )
    (comp (ref "R32")
      (value "2K Ohms")
      (footprint "eagle-import:RES0402")
      (libsource (lib "eagle-import") (part "RESISTOR-0402"))
    )
    (comp (ref "R33")
      (value "2K Ohms")
      (footprint "eagle-import:RES0402")
      (libsource (lib "eagle-import") (part "RESISTOR-0402"))
    )
    (comp (ref "R34")
      (value "1K Ohms")
      (footprint "eagle-import:RES0402")
      (libsource (lib "eagle-import") (part "RESISTOR-0402"))
    )
    (comp (ref "R35")
      (value "DNP")
      (footprint "eagle-import:RES0402")
      (libsource (lib "eagle-import") (part "RESISTOR-0402"))
    )
    (comp (ref "U4")
      (value "MCP4728-A0")
      (footprint "eagle-import:MSOP10")
      (libsource (lib "eagle-import") (part "MCP4728-A0"))
    )
    (comp (ref "U5")
      (value "MCP6V32-E/MNY")
      (footprint "eagle-import:TDFN8")
      (libsource (lib "eagle-import") (part "MCP6V32-E/MNY"))
    )
  )
  (nets
    (net (code "1") (name "1V5_RF_RX") (class "Default")
      (node (ref "C28") (pin "1") (pinfunction "C1_1") (pintype "passive"))
      (node (ref "C32") (pin "1") (pinfunction "C1_1") (pintype "passive"))
      (node (ref "P57") (pin "PAD_T") (pinfunction "TP_PAD_T") (pintype "input"))
      (node (ref "U8") (pin "1") (pinfunction "VOUT_1") (pintype "bidirectional"))
      (node (ref "U8") (pin "2") (pinfunction "SENSE_2") (pintype "bidirectional"))
    )
    (net (code "2") (name "1V8_RF_RX") (class "Default")
      (node (ref "C27") (pin "1") (pinfunction "C1_1") (pintype "passive"))
      (node (ref "C31") (pin "1") (pinfunction "C1_1") (pintype "passive"))
      (node (ref "C8") (pin "1") (pinfunction "C1_1") (pintype "passive"))
      (node (ref "P58") (pin "PAD_T") (pinfunction "TP_PAD_T") (pintype "input"))
      (node (ref "P59") (pin "PAD_T") (pinfunction "TP_PAD_T") (pintype "input"))
      (node (ref "R10") (pin "2") (pinfunction "2_2") (pintype "passive"))
      (node (ref "R15") (pin "2") (pinfunction "2_2") (pintype "passive"))
      (node (ref "R36") (pin "2") (pinfunction "2_2") (pintype "passive"))
      (node (ref "U3") (pin "16") (pinfunction "VCCB_16") (pintype "bidirectional"))
      (node (ref "U7") (pin "4") (pinfunction "SENSE/ADJ_4") (pintype "bidirectional"))
      (node (ref "U7") (pin "5") (pinfunction "VOUT_5") (pintype "bidirectional"))
    )
    (net (code "3") (name "1V8_RF_TX") (class "Default")
      (node (ref "C26") (pin "1") (pinfunction "C1_1") (pintype "passive"))
      (node (ref "C30") (pin "1") (pinfunction "C1_1") (pintype "passive"))
      (node (ref "C6") (pin "1") (pinfunction "C1_1") (pintype "passive"))
      (node (ref "P49") (pin "PAD_T") (pinfunction "TP_PAD_T") (pintype "input"))
      (node (ref "P50") (pin "PAD_T") (pinfunction "TP_PAD_T") (pintype "input"))
      (node (ref "R14") (pin "2") (pinfunction "2_2") (pintype "passive"))
      (node (ref "R36") (pin "1") (pinfunction "1_1") (pintype "passive"))
      (node (ref "R7") (pin "2") (pinfunction "2_2") (pintype "passive"))
      (node (ref "U2") (pin "16") (pinfunction "VCCB_16") (pintype "bidirectional"))
      (node (ref "U6") (pin "4") (pinfunction "SENSE/ADJ_4") (pintype "bidirectional"))
      (node (ref "U6") (pin "5") (pinfunction "VOUT_5") (pintype "bidirectional"))
    )
    (net (code "4") (name "2V5") (class "Default")
      (node (ref "JP3") (pin "2") (pinfunction "S_2") (pintype "passive"))
    )
    (net (code "5") (name "3V3") (class "Default")
      (node (ref "C1") (pin "1") (pinfunction "C1_1") (pintype "passive"))
      (node (ref "C10") (pin "1") (pinfunction "C1_1") (pintype "passive"))
      (node (ref "C16") (pin "1") (pinfunction "C1_1") (pintype "passive"))
      (node (ref "C17") (pin "1") (pinfunction "C1_1") (pintype "passive"))
      (node (ref "C18") (pin "1") (pinfunction "C1_1") (pintype "passive"))
      (node (ref "C19") (pin "1") (pinfunction "C1_1") (pintype "passive"))
      (node (ref "C2") (pin "1") (pinfunction "C1_1") (pintype "passive"))
      (node (ref "C21") (pin "1") (pinfunction "C1_1") (pintype "passive"))
      (node (ref "C22") (pin "1") (pinfunction "C1_1") (pintype "passive"))
      (node (ref "C23") (pin "1") (pinfunction "C1_1") (pintype "passive"))
      (node (ref "C7") (pin "1") (pinfunction "C1_1") (pintype "passive"))
      (node (ref "C9") (pin "1") (pinfunction "C1_1") (pintype "passive"))
      (node (ref "FB1") (pin "1") (pinfunction "1_1") (pintype "passive"))
      (node (ref "FB2") (pin "1") (pinfunction "1_1") (pintype "passive"))
      (node (ref "JP3") (pin "1") (pinfunction "S_1") (pintype "passive"))
      (node (ref "R1") (pin "2") (pinfunction "2_2") (pintype "passive"))
      (node (ref "R16") (pin "2") (pinfunction "2_2") (pintype "passive"))
      (node (ref "R2") (pin "2") (pinfunction "2_2") (pintype "passive"))
      (node (ref "R3") (pin "2") (pinfunction "2_2") (pintype "passive"))
      (node (ref "R4") (pin "2") (pinfunction "2_2") (pintype "passive"))
      (node (ref "R6") (pin "2") (pinfunction "2_2") (pintype "passive"))
      (node (ref "R9") (pin "2") (pinfunction "2_2") (pintype "passive"))
      (node (ref "TC1") (pin "1") (pinfunction "S_1") (pintype "passive"))
      (node (ref "U1") (pin "30") (pinfunction "VDDIN_30") (pintype "bidirectional"))
      (node (ref "U2") (pin "1") (pinfunction "VCCA_1") (pintype "bidirectional"))
      (node (ref "U2") (pin "10") (pinfunction "T/~{R}2_10") (pintype "bidirectional"))
      (node (ref "U2") (pin "15") (pinfunction "T/~{R}1_15") (pintype "bidirectional"))
      (node (ref "U2") (pin "2") (pinfunction "T/~{R}0_2") (pintype "bidirectional"))
      (node (ref "U3") (pin "1") (pinfunction "VCCA_1") (pintype "bidirectional"))
      (node (ref "U3") (pin "10") (pinfunction "T/~{R}2_10") (pintype "bidirectional"))
      (node (ref "U3") (pin "15") (pinfunction "T/~{R}1_15") (pintype "bidirectional"))
      (node (ref "U3") (pin "2") (pinfunction "T/~{R}0_2") (pintype "bidirectional"))
      (node (ref "U6") (pin "1") (pinfunction "VIN_1") (pintype "bidirectional"))
      (node (ref "U7") (pin "1") (pinfunction "VIN_1") (pintype "bidirectional"))
      (node (ref "U8") (pin "8") (pinfunction "VIN_8") (pintype "bidirectional"))
    )
    (net (code "6") (name "3V3_DAC_OPA") (class "Default")
      (node (ref "C11") (pin "1") (pinfunction "C1_1") (pintype "passive"))
      (node (ref "C12") (pin "1") (pinfunction "C1_1") (pintype "passive"))
      (node (ref "C13") (pin "1") (pinfunction "C1_1") (pintype "passive"))
      (node (ref "FB2") (pin "2") (pinfunction "2_2") (pintype "passive"))
      (node (ref "U4") (pin "1") (pinfunction "VDD_1") (pintype "bidirectional"))
      (node (ref "U5") (pin "8") (pinfunction "V+_8") (pintype "power_in"))
    )
    (net (code "7") (name "3V3_RF_RX") (class "Default")
      (node (ref "C42") (pin "1") (pinfunction "C1_1") (pintype "passive"))
      (node (ref "C44") (pin "1") (pinfunction "C1_1") (pintype "passive"))
      (node (ref "P60") (pin "PAD_T") (pinfunction "TP_PAD_T") (pintype "input"))
      (node (ref "P61") (pin "PAD_T") (pinfunction "TP_PAD_T") (pintype "input"))
      (node (ref "P62") (pin "PAD_T") (pinfunction "TP_PAD_T") (pintype "input"))
      (node (ref "P63") (pin "PAD_T") (pinfunction "TP_PAD_T") (pintype "input"))
      (node (ref "P64") (pin "PAD_T") (pinfunction "TP_PAD_T") (pintype "input"))
      (node (ref "P65") (pin "PAD_T") (pinfunction "TP_PAD_T") (pintype "input"))
      (node (ref "U11") (pin "1") (pinfunction "VOUT_1") (pintype "bidirectional"))
      (node (ref "U11") (pin "2") (pinfunction "VOUT_2") (pintype "bidirectional"))
      (node (ref "U11") (pin "3") (pinfunction "SENSE_3") (pintype "bidirectional"))
    )
    (net (code "8") (name "3V3_RF_TX") (class "Default")
      (node (ref "C41") (pin "1") (pinfunction "C1_1") (pintype "passive"))
      (node (ref "C43") (pin "1") (pinfunction "C1_1") (pintype "passive"))
      (node (ref "P51") (pin "PAD_T") (pinfunction "TP_PAD_T") (pintype "input"))
      (node (ref "P52") (pin "PAD_T") (pinfunction "TP_PAD_T") (pintype "input"))
      (node (ref "P53") (pin "PAD_T") (pinfunction "TP_PAD_T") (pintype "input"))
      (node (ref "P54") (pin "PAD_T") (pinfunction "TP_PAD_T") (pintype "input"))
      (node (ref "P55") (pin "PAD_T") (pinfunction "TP_PAD_T") (pintype "input"))
      (node (ref "P56") (pin "PAD_T") (pinfunction "TP_PAD_T") (pintype "input"))
      (node (ref "U10") (pin "1") (pinfunction "VOUT_1") (pintype "bidirectional"))
      (node (ref "U10") (pin "2") (pinfunction "VOUT_2") (pintype "bidirectional"))
      (node (ref "U10") (pin "3") (pinfunction "SENSE_3") (pintype "bidirectional"))
    )
    (net (code "9") (name "5V0") (class "Default")
      (node (ref "C20") (pin "1") (pinfunction "C1_1") (pintype "passive"))
      (node (ref "C24") (pin "1") (pinfunction "C1_1") (pintype "passive"))
      (node (ref "C34") (pin "1") (pinfunction "C1_1") (pintype "passive"))
      (node (ref "C35") (pin "1") (pinfunction "C1_1") (pintype "passive"))
      (node (ref "C36") (pin "1") (pinfunction "C1_1") (pintype "passive"))
      (node (ref "C37") (pin "1") (pinfunction "C1_1") (pintype "passive"))
      (node (ref "C38") (pin "1") (pinfunction "C1_1") (pintype "passive"))
      (node (ref "JP3") (pin "5") (pinfunction "S_5") (pintype "passive"))
      (node (ref "JP3") (pin "6") (pinfunction "S_6") (pintype "passive"))
      (node (ref "U10") (pin "7") (pinfunction "VIN_7") (pintype "bidirectional"))
      (node (ref "U10") (pin "8") (pinfunction "VIN_8") (pintype "bidirectional"))
      (node (ref "U11") (pin "7") (pinfunction "VIN_7") (pintype "bidirectional"))
      (node (ref "U11") (pin "8") (pinfunction "VIN_8") (pintype "bidirectional"))
      (node (ref "U9") (pin "7") (pinfunction "VIN_7") (pintype "bidirectional"))
      (node (ref "U9") (pin "8") (pinfunction "VIN_8") (pintype "bidirectional"))
    )
    (net (code "10") (name "5V0_RF_LO") (class "Default")
      (node (ref "C29") (pin "1") (pinfunction "C1_1") (pintype "passive"))
      (node (ref "C33") (pin "1") (pinfunction "C1_1") (pintype "passive"))
      (node (ref "P66") (pin "PAD_T") (pinfunction "TP_PAD_T") (pintype "input"))
      (node (ref "P67") (pin "PAD_T") (pinfunction "TP_PAD_T") (pintype "input"))
      (node (ref "U9") (pin "1") (pinfunction "VOUT_1") (pintype "bidirectional"))
      (node (ref "U9") (pin "2") (pinfunction "VOUT_2") (pintype "bidirectional"))
      (node (ref "U9") (pin "3") (pinfunction "SENSE_3") (pintype "bidirectional"))
    )
    (net (code "11") (name "DAC_I2C_SCL") (class "Default")
      (node (ref "R1") (pin "1") (pinfunction "1_1") (pintype "passive"))
      (node (ref "U1") (pin "12") (pinfunction "PA09_12") (pintype "bidirectional"))
      (node (ref "U4") (pin "2") (pinfunction "SCL_2") (pintype "bidirectional"))
    )
    (net (code "12") (name "DAC_I2C_SDA") (class "Default")
      (node (ref "R2") (pin "1") (pinfunction "1_1") (pintype "passive"))
      (node (ref "U1") (pin "11") (pinfunction "PA08_11") (pintype "bidirectional"))
      (node (ref "U4") (pin "3") (pinfunction "SDA_3") (pintype "bidirectional"))
    )
    (net (code "13") (name "EXT_CLK_2_3") (class "Default")
      (node (ref "JP2") (pin "3") (pinfunction "S_3") (pintype "passive"))
    )
    (net (code "14") (name "EXT_IO_1_3") (class "Default")
      (node (ref "JP1") (pin "4") (pinfunction "S_4") (pintype "passive"))
      (node (ref "U1") (pin "15") (pinfunction "PA14_15") (pintype "bidirectional"))
    )
    (net (code "15") (name "EXT_IO_1_4") (class "Default")
      (node (ref "JP1") (pin "3") (pinfunction "S_3") (pintype "passive"))
      (node (ref "U1") (pin "16") (pinfunction "PA15_16") (pintype "bidirectional"))
    )
    (net (code "16") (name "EXT_IO_1_5") (class "Default")
      (node (ref "JP1") (pin "6") (pinfunction "S_6") (pintype "passive"))
      (node (ref "U1") (pin "24") (pinfunction "PA25_24") (pintype "bidirectional"))
    )
    (net (code "17") (name "EXT_IO_2_2") (class "Default")
      (node (ref "JP2") (pin "6") (pinfunction "S_6") (pintype "passive"))
    )
    (net (code "18") (name "EXT_IO_2_4") (class "Default")
      (node (ref "JP2") (pin "4") (pinfunction "S_4") (pintype "passive"))
    )
    (net (code "19") (name "EXT_IO_2_6") (class "Default")
      (node (ref "JP2") (pin "2") (pinfunction "S_2") (pintype "passive"))
    )
    (net (code "20") (name "GND") (class "Default")
      (node (ref "C1") (pin "2") (pinfunction "C2_2") (pintype "passive"))
      (node (ref "C10") (pin "2") (pinfunction "C2_2") (pintype "passive"))
      (node (ref "C11") (pin "2") (pinfunction "C2_2") (pintype "passive"))
      (node (ref "C12") (pin "2") (pinfunction "C2_2") (pintype "passive"))
      (node (ref "C13") (pin "2") (pinfunction "C2_2") (pintype "passive"))
      (node (ref "C14") (pin "2") (pinfunction "C2_2") (pintype "passive"))
      (node (ref "C15") (pin "2") (pinfunction "C2_2") (pintype "passive"))
      (node (ref "C16") (pin "2") (pinfunction "C2_2") (pintype "passive"))
      (node (ref "C17") (pin "2") (pinfunction "C2_2") (pintype "passive"))
      (node (ref "C18") (pin "2") (pinfunction "C2_2") (pintype "passive"))
      (node (ref "C19") (pin "2") (pinfunction "C2_2") (pintype "passive"))
      (node (ref "C2") (pin "2") (pinfunction "C2_2") (pintype "passive"))
      (node (ref "C20") (pin "2") (pinfunction "C2_2") (pintype "passive"))
      (node (ref "C21") (pin "2") (pinfunction "C2_2") (pintype "passive"))
      (node (ref "C22") (pin "2") (pinfunction "C2_2") (pintype "passive"))
      (node (ref "C23") (pin "2") (pinfunction "C2_2") (pintype "passive"))
      (node (ref "C24") (pin "2") (pinfunction "C2_2") (pintype "passive"))
      (node (ref "C25") (pin "2") (pinfunction "C2_2") (pintype "passive"))
      (node (ref "C26") (pin "2") (pinfunction "C2_2") (pintype "passive"))
      (node (ref "C27") (pin "2") (pinfunction "C2_2") (pintype "passive"))
      (node (ref "C28") (pin "2") (pinfunction "C2_2") (pintype "passive"))
      (node (ref "C29") (pin "2") (pinfunction "C2_2") (pintype "passive"))
      (node (ref "C3") (pin "2") (pinfunction "C2_2") (pintype "passive"))
      (node (ref "C30") (pin "2") (pinfunction "C2_2") (pintype "passive"))
      (node (ref "C31") (pin "2") (pinfunction "C2_2") (pintype "passive"))
      (node (ref "C32") (pin "2") (pinfunction "C2_2") (pintype "passive"))
      (node (ref "C33") (pin "2") (pinfunction "C2_2") (pintype "passive"))
      (node (ref "C34") (pin "2") (pinfunction "C2_2") (pintype "passive"))
      (node (ref "C35") (pin "2") (pinfunction "C2_2") (pintype "passive"))
      (node (ref "C36") (pin "2") (pinfunction "C2_2") (pintype "passive"))
      (node (ref "C37") (pin "2") (pinfunction "C2_2") (pintype "passive"))
      (node (ref "C38") (pin "2") (pinfunction "C2_2") (pintype "passive"))
      (node (ref "C39") (pin "2") (pinfunction "C2_2") (pintype "passive"))
      (node (ref "C4") (pin "2") (pinfunction "C2_2") (pintype "passive"))
      (node (ref "C40") (pin "2") (pinfunction "C2_2") (pintype "passive"))
      (node (ref "C41") (pin "2") (pinfunction "C2_2") (pintype "passive"))
      (node (ref "C42") (pin "2") (pinfunction "C2_2") (pintype "passive"))
      (node (ref "C43") (pin "2") (pinfunction "C2_2") (pintype "passive"))
      (node (ref "C44") (pin "2") (pinfunction "C2_2") (pintype "passive"))
      (node (ref "C5") (pin "2") (pinfunction "C2_2") (pintype "passive"))
      (node (ref "C6") (pin "2") (pinfunction "C2_2") (pintype "passive"))
      (node (ref "C7") (pin "2") (pinfunction "C2_2") (pintype "passive"))
      (node (ref "C8") (pin "2") (pinfunction "C2_2") (pintype "passive"))
      (node (ref "C9") (pin "2") (pinfunction "C2_2") (pintype "passive"))
      (node (ref "JP1") (pin "5") (pinfunction "S_5") (pintype "passive"))
      (node (ref "JP2") (pin "1") (pinfunction "S_1") (pintype "passive"))
      (node (ref "JP2") (pin "5") (pinfunction "S_5") (pintype "passive"))
      (node (ref "JP3") (pin "3") (pinfunction "S_3") (pintype "passive"))
      (node (ref "JP3") (pin "4") (pinfunction "S_4") (pintype "passive"))
      (node (ref "P10") (pin "PAD_T") (pinfunction "TP_PAD_T") (pintype "input"))
      (node (ref "P11") (pin "PAD_T") (pinfunction "TP_PAD_T") (pintype "input"))
      (node (ref "P12") (pin "PAD_T") (pinfunction "TP_PAD_T") (pintype "input"))
      (node (ref "P13") (pin "PAD_T") (pinfunction "TP_PAD_T") (pintype "input"))
      (node (ref "P14") (pin "PAD_T") (pinfunction "TP_PAD_T") (pintype "input"))
      (node (ref "P15") (pin "PAD_T") (pinfunction "TP_PAD_T") (pintype "input"))
      (node (ref "P16") (pin "PAD_T") (pinfunction "TP_PAD_T") (pintype "input"))
      (node (ref "P17") (pin "PAD_T") (pinfunction "TP_PAD_T") (pintype "input"))
      (node (ref "P18") (pin "PAD_T") (pinfunction "TP_PAD_T") (pintype "input"))
      (node (ref "P19") (pin "PAD_T") (pinfunction "TP_PAD_T") (pintype "input"))
      (node (ref "P20") (pin "PAD_T") (pinfunction "TP_PAD_T") (pintype "input"))
      (node (ref "P21") (pin "PAD_T") (pinfunction "TP_PAD_T") (pintype "input"))
      (node (ref "P22") (pin "PAD_T") (pinfunction "TP_PAD_T") (pintype "input"))
      (node (ref "P23") (pin "PAD_T") (pinfunction "TP_PAD_T") (pintype "input"))
      (node (ref "P24") (pin "PAD_T") (pinfunction "TP_PAD_T") (pintype "input"))
      (node (ref "P25") (pin "PAD_T") (pinfunction "TP_PAD_T") (pintype "input"))
      (node (ref "P26") (pin "PAD_T") (pinfunction "TP_PAD_T") (pintype "input"))
      (node (ref "P27") (pin "PAD_T") (pinfunction "TP_PAD_T") (pintype "input"))
      (node (ref "P28") (pin "PAD_T") (pinfunction "TP_PAD_T") (pintype "input"))
      (node (ref "P29") (pin "PAD_T") (pinfunction "TP_PAD_T") (pintype "input"))
      (node (ref "P30") (pin "PAD_T") (pinfunction "TP_PAD_T") (pintype "input"))
      (node (ref "P31") (pin "PAD_T") (pinfunction "TP_PAD_T") (pintype "input"))
      (node (ref "P32") (pin "PAD_T") (pinfunction "TP_PAD_T") (pintype "input"))
      (node (ref "P33") (pin "PAD_T") (pinfunction "TP_PAD_T") (pintype "input"))
      (node (ref "P34") (pin "PAD_T") (pinfunction "TP_PAD_T") (pintype "input"))
      (node (ref "P41") (pin "PAD_T") (pinfunction "TP_PAD_T") (pintype "input"))
      (node (ref "P42") (pin "PAD_T") (pinfunction "TP_PAD_T") (pintype "input"))
      (node (ref "P6") (pin "PAD_T") (pinfunction "TP_PAD_T") (pintype "input"))
      (node (ref "P7") (pin "PAD_T") (pinfunction "TP_PAD_T") (pintype "input"))
      (node (ref "P8") (pin "PAD_T") (pinfunction "TP_PAD_T") (pintype "input"))
      (node (ref "P9") (pin "PAD_T") (pinfunction "TP_PAD_T") (pintype "input"))
      (node (ref "Q1") (pin "2") (pinfunction "S_2") (pintype "passive"))
      (node (ref "Q2") (pin "2") (pinfunction "S_2") (pintype "passive"))
      (node (ref "R11") (pin "1") (pinfunction "1_1") (pintype "passive"))
      (node (ref "R12") (pin "2") (pinfunction "2_2") (pintype "passive"))
      (node (ref "R21") (pin "2") (pinfunction "2_2") (pintype "passive"))
      (node (ref "R30") (pin "1") (pinfunction "1_1") (pintype "passive"))
      (node (ref "R34") (pin "1") (pinfunction "1_1") (pintype "passive"))
      (node (ref "R35") (pin "1") (pinfunction "1_1") (pintype "passive"))
      (node (ref "R37") (pin "1") (pinfunction "1_1") (pintype "passive"))
      (node (ref "R38") (pin "1") (pinfunction "1_1") (pintype "passive"))
      (node (ref "R39") (pin "1") (pinfunction "1_1") (pintype "passive"))
      (node (ref "R40") (pin "1") (pinfunction "1_1") (pintype "passive"))
      (node (ref "R41") (pin "1") (pinfunction "1_1") (pintype "passive"))
      (node (ref "R5") (pin "1") (pinfunction "1_1") (pintype "passive"))
      (node (ref "R8") (pin "1") (pinfunction "1_1") (pintype "passive"))
      (node (ref "TC1") (pin "3") (pinfunction "S_3") (pintype "passive"))
      (node (ref "U1") (pin "10") (pinfunction "GND_10") (pintype "bidirectional"))
      (node (ref "U1") (pin "28") (pinfunction "GND_28") (pintype "bidirectional"))
      (node (ref "U1") (pin "33") (pinfunction "GND_33") (pintype "bidirectional"))
      (node (ref "U10") (pin "6") (pinfunction "GND_6") (pintype "bidirectional"))
      (node (ref "U10") (pin "9") (pinfunction "GND_9") (pintype "bidirectional"))
      (node (ref "U11") (pin "6") (pinfunction "GND_6") (pintype "bidirectional"))
      (node (ref "U11") (pin "9") (pinfunction "GND_9") (pintype "bidirectional"))
      (node (ref "U2") (pin "17") (pinfunction "GND_17") (pintype "bidirectional"))
      (node (ref "U2") (pin "7") (pinfunction "T/~{R}3_7") (pintype "bidirectional"))
      (node (ref "U2") (pin "8") (pinfunction "GND_8") (pintype "bidirectional"))
      (node (ref "U3") (pin "17") (pinfunction "GND_17") (pintype "bidirectional"))
      (node (ref "U3") (pin "7") (pinfunction "T/~{R}3_7") (pintype "bidirectional"))
      (node (ref "U3") (pin "8") (pinfunction "GND_8") (pintype "bidirectional"))
      (node (ref "U4") (pin "10") (pinfunction "VSS_10") (pintype "bidirectional"))
      (node (ref "U4") (pin "4") (pinfunction "~{LDAC}_4") (pintype "bidirectional"))
      (node (ref "U5") (pin "4") (pinfunction "V-_4") (pintype "power_in"))
      (node (ref "U5") (pin "9") (pinfunction "V-_9") (pintype "power_in"))
      (node (ref "U6") (pin "2") (pinfunction "GND_2") (pintype "bidirectional"))
      (node (ref "U7") (pin "2") (pinfunction "GND_2") (pintype "bidirectional"))
      (node (ref "U8") (pin "3") (pinfunction "GND_3") (pintype "bidirectional"))
      (node (ref "U8") (pin "6") (pinfunction "GND_6") (pintype "bidirectional"))
      (node (ref "U8") (pin "9") (pinfunction "GND_9") (pintype "bidirectional"))
      (node (ref "U9") (pin "6") (pinfunction "GND_6") (pintype "bidirectional"))
      (node (ref "U9") (pin "9") (pinfunction "GND_9") (pintype "bidirectional"))
    )
    (net (code "21") (name "LED") (class "Default")
      (node (ref "D1") (pin "A") (pinfunction "A_A") (pintype "passive"))
      (node (ref "U1") (pin "14") (pinfunction "PA11_14") (pintype "bidirectional"))
    )
    (net (code "22") (name "LO_ANA_PWR_EN") (class "Default")
      (node (ref "R37") (pin "2") (pinfunction "2_2") (pintype "passive"))
      (node (ref "U1") (pin "1") (pinfunction "PA00_1") (pintype "bidirectional"))
      (node (ref "U9") (pin "5") (pinfunction "EN_5") (pintype "bidirectional"))
    )
    (net (code "23") (name "MCU_I2C_SCL") (class "Default")
      (node (ref "JP1") (pin "2") (pinfunction "S_2") (pintype "passive"))
      (node (ref "R3") (pin "1") (pinfunction "1_1") (pintype "passive"))
      (node (ref "U1") (pin "18") (pinfunction "PA17_18") (pintype "bidirectional"))
    )
    (net (code "24") (name "MCU_I2C_SDA") (class "Default")
      (node (ref "JP1") (pin "1") (pinfunction "S_1") (pintype "passive"))
      (node (ref "R4") (pin "1") (pinfunction "1_1") (pintype "passive"))
      (node (ref "U1") (pin "17") (pinfunction "PA16_17") (pintype "bidirectional"))
    )
    (net (code "25") (name "MCU_SWO") (class "Default")
      (node (ref "TC1") (pin "6") (pinfunction "S_6") (pintype "passive"))
      (node (ref "U1") (pin "19") (pinfunction "PA18_19") (pintype "bidirectional"))
    )
    (net (code "26") (name "Net-(C3-C1)") (class "Default")
      (node (ref "C3") (pin "1") (pinfunction "C1_1") (pintype "passive"))
      (node (ref "C4") (pin "1") (pinfunction "C1_1") (pintype "passive"))
      (node (ref "FB1") (pin "2") (pinfunction "2_2") (pintype "passive"))
      (node (ref "U1") (pin "9") (pinfunction "VDDANA_9") (pintype "bidirectional"))
    )
    (net (code "27") (name "Net-(C5-C1)") (class "Default")
      (node (ref "C5") (pin "1") (pinfunction "C1_1") (pintype "passive"))
      (node (ref "U1") (pin "29") (pinfunction "VDDCORE_29") (pintype "bidirectional"))
    )
    (net (code "28") (name "Net-(C25-C1)") (class "Default")
      (node (ref "C25") (pin "1") (pinfunction "C1_1") (pintype "passive"))
      (node (ref "U9") (pin "4") (pinfunction "SS_4") (pintype "bidirectional"))
    )
    (net (code "29") (name "Net-(C39-C1)") (class "Default")
      (node (ref "C39") (pin "1") (pinfunction "C1_1") (pintype "passive"))
      (node (ref "U10") (pin "4") (pinfunction "SS_4") (pintype "bidirectional"))
    )
    (net (code "30") (name "Net-(C40-C1)") (class "Default")
      (node (ref "C40") (pin "1") (pinfunction "C1_1") (pintype "passive"))
      (node (ref "U11") (pin "4") (pinfunction "SS_4") (pintype "bidirectional"))
    )
    (net (code "31") (name "Net-(D1-PadC)") (class "Default")
      (node (ref "D1") (pin "C") (pinfunction "C_C") (pintype "passive"))
      (node (ref "R5") (pin "2") (pinfunction "2_2") (pintype "passive"))
    )
    (net (code "32") (name "Net-(P2-TP)") (class "Default")
      (node (ref "P2") (pin "PAD_T") (pinfunction "TP_PAD_T") (pintype "input"))
      (node (ref "R17") (pin "1") (pinfunction "1_1") (pintype "passive"))
    )
    (net (code "33") (name "Net-(P3-TP)") (class "Default")
      (node (ref "P3") (pin "PAD_T") (pinfunction "TP_PAD_T") (pintype "input"))
      (node (ref "R19") (pin "1") (pinfunction "1_1") (pintype "passive"))
    )
    (net (code "34") (name "Net-(P4-TP)") (class "Default")
      (node (ref "P4") (pin "PAD_T") (pinfunction "TP_PAD_T") (pintype "input"))
      (node (ref "R18") (pin "1") (pinfunction "1_1") (pintype "passive"))
    )
    (net (code "35") (name "Net-(P5-TP)") (class "Default")
      (node (ref "P5") (pin "PAD_T") (pinfunction "TP_PAD_T") (pintype "input"))
      (node (ref "R20") (pin "1") (pinfunction "1_1") (pintype "passive"))
    )
    (net (code "36") (name "Net-(P36-TP)") (class "Default")
      (node (ref "P36") (pin "PAD_T") (pinfunction "TP_PAD_T") (pintype "input"))
      (node (ref "R23") (pin "1") (pinfunction "1_1") (pintype "passive"))
    )
    (net (code "37") (name "Net-(P37-TP)") (class "Default")
      (node (ref "P37") (pin "PAD_T") (pinfunction "TP_PAD_T") (pintype "input"))
      (node (ref "R26") (pin "1") (pinfunction "1_1") (pintype "passive"))
    )
    (net (code "38") (name "Net-(P38-TP)") (class "Default")
      (node (ref "P38") (pin "PAD_T") (pinfunction "TP_PAD_T") (pintype "input"))
      (node (ref "R24") (pin "1") (pinfunction "1_1") (pintype "passive"))
    )
    (net (code "39") (name "Net-(P39-TP)") (class "Default")
      (node (ref "P39") (pin "PAD_T") (pinfunction "TP_PAD_T") (pintype "input"))
      (node (ref "R27") (pin "1") (pinfunction "1_1") (pintype "passive"))
    )
    (net (code "40") (name "Net-(P40-TP)") (class "Default")
      (node (ref "P40") (pin "PAD_T") (pinfunction "TP_PAD_T") (pintype "input"))
      (node (ref "R25") (pin "1") (pinfunction "1_1") (pintype "passive"))
    )
    (net (code "41") (name "Net-(U2-~{OE})") (class "Default")
      (node (ref "R12") (pin "1") (pinfunction "1_1") (pintype "passive"))
      (node (ref "R13") (pin "2") (pinfunction "2_2") (pintype "passive"))
      (node (ref "U2") (pin "9") (pinfunction "~{OE}_9") (pintype "bidirectional"))
    )
    (net (code "42") (name "Net-(U3-~{OE})") (class "Default")
      (node (ref "R21") (pin "1") (pinfunction "1_1") (pintype "passive"))
      (node (ref "R22") (pin "2") (pinfunction "2_2") (pintype "passive"))
      (node (ref "U3") (pin "9") (pinfunction "~{OE}_9") (pintype "bidirectional"))
    )
    (net (code "43") (name "Net-(U5A-+IN)") (class "Default")
      (node (ref "R29") (pin "1") (pinfunction "1_1") (pintype "passive"))
      (node (ref "R30") (pin "2") (pinfunction "2_2") (pintype "passive"))
      (node (ref "U5") (pin "3") (pinfunction "+IN_3") (pintype "input"))
    )
    (net (code "44") (name "Net-(U5A--IN)") (class "Default")
      (node (ref "R28") (pin "1") (pinfunction "1_1") (pintype "passive"))
      (node (ref "R31") (pin "2") (pinfunction "2_2") (pintype "passive"))
      (node (ref "U5") (pin "2") (pinfunction "-IN_2") (pintype "input"))
    )
    (net (code "45") (name "Net-(U5A-OUT)") (class "Default")
      (node (ref "R31") (pin "1") (pinfunction "1_1") (pintype "passive"))
      (node (ref "R33") (pin "2") (pinfunction "2_2") (pintype "passive"))
      (node (ref "U5") (pin "1") (pinfunction "OUT_1") (pintype "output"))
    )
    (net (code "46") (name "Net-(U5B--IN)") (class "Default")
      (node (ref "R32") (pin "2") (pinfunction "2_2") (pintype "passive"))
      (node (ref "U5") (pin "6") (pinfunction "-IN_6") (pintype "input"))
      (node (ref "U5") (pin "7") (pinfunction "OUT_7") (pintype "output"))
    )
    (net (code "47") (name "RF_SPI_MISO") (class "Default")
      (node (ref "U1") (pin "6") (pinfunction "PA05_6") (pintype "bidirectional"))
      (node (ref "U2") (pin "6") (pinfunction "A3_6") (pintype "bidirectional"))
      (node (ref "U3") (pin "6") (pinfunction "A3_6") (pintype "bidirectional"))
    )
    (net (code "48") (name "RF_SPI_MOSI") (class "Default")
      (node (ref "U1") (pin "7") (pinfunction "PA06_7") (pintype "bidirectional"))
      (node (ref "U2") (pin "5") (pinfunction "A2_5") (pintype "bidirectional"))
      (node (ref "U3") (pin "5") (pinfunction "A2_5") (pintype "bidirectional"))
    )
    (net (code "49") (name "RF_SPI_SCK") (class "Default")
      (node (ref "U1") (pin "8") (pinfunction "PA07_8") (pintype "bidirectional"))
      (node (ref "U2") (pin "4") (pinfunction "A1_4") (pintype "bidirectional"))
      (node (ref "U3") (pin "4") (pinfunction "A1_4") (pintype "bidirectional"))
    )
    (net (code "50") (name "RX_ANA_PWR_EN") (class "Default")
      (node (ref "R38") (pin "2") (pinfunction "2_2") (pintype "passive"))
      (node (ref "U1") (pin "20") (pinfunction "PA19_20") (pintype "bidirectional"))
      (node (ref "U11") (pin "5") (pinfunction "EN_5") (pintype "bidirectional"))
      (node (ref "U8") (pin "5") (pinfunction "EN/UVLO_5") (pintype "bidirectional"))
    )
    (net (code "51") (name "RX_DIG_PWR_EN") (class "Default")
      (node (ref "R40") (pin "2") (pinfunction "2_2") (pintype "passive"))
      (node (ref "U1") (pin "21") (pinfunction "PA22_21") (pintype "bidirectional"))
      (node (ref "U7") (pin "3") (pinfunction "EN_3") (pintype "bidirectional"))
    )
    (net (code "52") (name "RX_GAIN_VCTRL") (class "Default")
      (node (ref "P44") (pin "PAD_T") (pinfunction "TP_PAD_T") (pintype "input"))
      (node (ref "U4") (pin "6") (pinfunction "VOUTA_6") (pintype "bidirectional"))
    )
    (net (code "53") (name "RX_PWR_VDET") (class "Default")
      (node (ref "P43") (pin "PAD_T") (pinfunction "TP_PAD_T") (pintype "input"))
      (node (ref "U5") (pin "5") (pinfunction "+IN_5") (pintype "input"))
    )
    (net (code "54") (name "RX_PWR_VDET_DIV") (class "Default")
      (node (ref "C14") (pin "1") (pinfunction "C1_1") (pintype "passive"))
      (node (ref "R32") (pin "1") (pinfunction "1_1") (pintype "passive"))
      (node (ref "R34") (pin "2") (pinfunction "2_2") (pintype "passive"))
      (node (ref "U1") (pin "4") (pinfunction "PA03_4") (pintype "bidirectional"))
    )
    (net (code "55") (name "RX_RST") (class "Default")
      (node (ref "Q1") (pin "1") (pinfunction "G_1") (pintype "passive"))
      (node (ref "R8") (pin "2") (pinfunction "2_2") (pintype "passive"))
      (node (ref "U1") (pin "25") (pinfunction "PA27_25") (pintype "bidirectional"))
    )
    (net (code "56") (name "RX_SPI_MISO_1V8") (class "Default")
      (node (ref "R18") (pin "2") (pinfunction "2_2") (pintype "passive"))
      (node (ref "U3") (pin "11") (pinfunction "B3_11") (pintype "bidirectional"))
    )
    (net (code "57") (name "RX_SPI_MOSI_1V8") (class "Default")
      (node (ref "R20") (pin "2") (pinfunction "2_2") (pintype "passive"))
      (node (ref "U3") (pin "12") (pinfunction "B2_12") (pintype "bidirectional"))
    )
    (net (code "58") (name "RX_SPI_SCK_1V8") (class "Default")
      (node (ref "R19") (pin "2") (pinfunction "2_2") (pintype "passive"))
      (node (ref "U3") (pin "13") (pinfunction "B1_13") (pintype "bidirectional"))
    )
    (net (code "59") (name "SWCLK") (class "Default")
      (node (ref "TC1") (pin "4") (pinfunction "S_4") (pintype "passive"))
      (node (ref "U1") (pin "31") (pinfunction "PA30_31") (pintype "bidirectional"))
    )
    (net (code "60") (name "SWDIO") (class "Default")
      (node (ref "TC1") (pin "2") (pinfunction "S_2") (pintype "passive"))
      (node (ref "U1") (pin "32") (pinfunction "PA31_32") (pintype "bidirectional"))
    )
    (net (code "61") (name "TX_ANA_PWR_EN") (class "Default")
      (node (ref "R39") (pin "2") (pinfunction "2_2") (pintype "passive"))
      (node (ref "U1") (pin "2") (pinfunction "PA01_2") (pintype "bidirectional"))
      (node (ref "U10") (pin "5") (pinfunction "EN_5") (pintype "bidirectional"))
    )
    (net (code "62") (name "TX_DIG_PWR_EN") (class "Default")
      (node (ref "R41") (pin "2") (pinfunction "2_2") (pintype "passive"))
      (node (ref "U1") (pin "22") (pinfunction "PA23_22") (pintype "bidirectional"))
      (node (ref "U6") (pin "3") (pinfunction "EN_3") (pintype "bidirectional"))
    )
    (net (code "63") (name "TX_GAIN_VCTRL1") (class "Default")
      (node (ref "P45") (pin "PAD_T") (pinfunction "TP_PAD_T") (pintype "input"))
      (node (ref "U4") (pin "9") (pinfunction "VOUTD_9") (pintype "bidirectional"))
    )
    (net (code "64") (name "TX_GAIN_VCTRL2") (class "Default")
      (node (ref "P46") (pin "PAD_T") (pinfunction "TP_PAD_T") (pintype "input"))
      (node (ref "U4") (pin "8") (pinfunction "VOUTC_8") (pintype "bidirectional"))
    )
    (net (code "65") (name "TX_PWR_VDET_DIV") (class "Default")
      (node (ref "C15") (pin "1") (pinfunction "C1_1") (pintype "passive"))
      (node (ref "R33") (pin "1") (pinfunction "1_1") (pintype "passive"))
      (node (ref "R35") (pin "2") (pinfunction "2_2") (pintype "passive"))
      (node (ref "U1") (pin "3") (pinfunction "PA02_3") (pintype "bidirectional"))
    )
    (net (code "66") (name "TX_PWR_VDET_N") (class "Default")
      (node (ref "P48") (pin "PAD_T") (pinfunction "TP_PAD_T") (pintype "input"))
      (node (ref "R28") (pin "2") (pinfunction "2_2") (pintype "passive"))
    )
    (net (code "67") (name "TX_PWR_VDET_P") (class "Default")
      (node (ref "P47") (pin "PAD_T") (pinfunction "TP_PAD_T") (pintype "input"))
      (node (ref "R29") (pin "2") (pinfunction "2_2") (pintype "passive"))
    )
    (net (code "68") (name "TX_RST") (class "Default")
      (node (ref "Q2") (pin "1") (pinfunction "G_1") (pintype "passive"))
      (node (ref "R11") (pin "2") (pinfunction "2_2") (pintype "passive"))
      (node (ref "U1") (pin "5") (pinfunction "PA04_5") (pintype "bidirectional"))
    )
    (net (code "69") (name "TX_SPI_MISO_1V8") (class "Default")
      (node (ref "R27") (pin "2") (pinfunction "2_2") (pintype "passive"))
      (node (ref "U2") (pin "11") (pinfunction "B3_11") (pintype "bidirectional"))
    )
    (net (code "70") (name "TX_SPI_MOSI_1V8") (class "Default")
      (node (ref "R25") (pin "2") (pinfunction "2_2") (pintype "passive"))
      (node (ref "U2") (pin "12") (pinfunction "B2_12") (pintype "bidirectional"))
    )
    (net (code "71") (name "TX_SPI_SCK_1V8") (class "Default")
      (node (ref "R24") (pin "2") (pinfunction "2_2") (pintype "passive"))
      (node (ref "U2") (pin "13") (pinfunction "B1_13") (pintype "bidirectional"))
    )
    (net (code "72") (name "unconnected-(TC1F-S-Pad5)") (class "Default")
      (node (ref "TC1") (pin "5") (pinfunction "S_5") (pintype "passive"))
    )
    (net (code "73") (name "unconnected-(U1-PA24-Pad23)") (class "Default")
      (node (ref "U1") (pin "23") (pinfunction "PA24_23") (pintype "bidirectional"))
    )
    (net (code "74") (name "unconnected-(U4-VOUTB-Pad7)") (class "Default")
      (node (ref "U4") (pin "7") (pinfunction "VOUTB_7") (pintype "bidirectional"))
    )
    (net (code "75") (name "unconnected-(U4-~{BSY}-Pad5)") (class "Default")
      (node (ref "U4") (pin "5") (pinfunction "~{BSY}_5") (pintype "bidirectional"))
    )
    (net (code "76") (name "unconnected-(U8-PG-Pad7)") (class "Default")
      (node (ref "U8") (pin "7") (pinfunction "PG_7") (pintype "bidirectional"))
    )
    (net (code "77") (name "~{MCU_RESET}") (class "Default")
      (node (ref "R6") (pin "1") (pinfunction "1_1") (pintype "passive"))
      (node (ref "TC1") (pin "10") (pinfunction "S_10") (pintype "passive"))
      (node (ref "U1") (pin "26") (pinfunction "~{RESET}_26") (pintype "bidirectional"))
    )
    (net (code "78") (name "~{RX_RST_1V8}") (class "Default")
      (node (ref "P1") (pin "PAD_T") (pinfunction "TP_PAD_T") (pintype "input"))
      (node (ref "Q1") (pin "3") (pinfunction "D_3") (pintype "passive"))
      (node (ref "R10") (pin "1") (pinfunction "1_1") (pintype "passive"))
    )
    (net (code "79") (name "~{RX_SPI_CS_1V8}") (class "Default")
      (node (ref "R15") (pin "1") (pinfunction "1_1") (pintype "passive"))
      (node (ref "R17") (pin "2") (pinfunction "2_2") (pintype "passive"))
      (node (ref "U3") (pin "14") (pinfunction "B0_14") (pintype "bidirectional"))
    )
    (net (code "80") (name "~{RX_SPI_CS}") (class "Default")
      (node (ref "R16") (pin "1") (pinfunction "1_1") (pintype "passive"))
      (node (ref "R22") (pin "1") (pinfunction "1_1") (pintype "passive"))
      (node (ref "U1") (pin "27") (pinfunction "PA28_27") (pintype "bidirectional"))
      (node (ref "U3") (pin "3") (pinfunction "A0_3") (pintype "bidirectional"))
    )
    (net (code "81") (name "~{TX_RST_1V8}") (class "Default")
      (node (ref "P35") (pin "PAD_T") (pinfunction "TP_PAD_T") (pintype "input"))
      (node (ref "Q2") (pin "3") (pinfunction "D_3") (pintype "passive"))
      (node (ref "R14") (pin "1") (pinfunction "1_1") (pintype "passive"))
    )
    (net (code "82") (name "~{TX_SPI_CS_1V8}") (class "Default")
      (node (ref "R23") (pin "2") (pinfunction "2_2") (pintype "passive"))
      (node (ref "R26") (pin "2") (pinfunction "2_2") (pintype "passive"))
      (node (ref "R7") (pin "1") (pinfunction "1_1") (pintype "passive"))
      (node (ref "U2") (pin "14") (pinfunction "B0_14") (pintype "bidirectional"))
    )
    (net (code "83") (name "~{TX_SPI_CS}") (class "Default")
      (node (ref "R13") (pin "1") (pinfunction "1_1") (pintype "passive"))
      (node (ref "R9") (pin "1") (pinfunction "1_1") (pintype "passive"))
      (node (ref "U1") (pin "13") (pinfunction "PA10_13") (pintype "bidirectional"))
      (node (ref "U2") (pin "3") (pinfunction "A0_3") (pintype "bidirectional"))
    )
  )
)
